# ROM16word.net
KiCad netlist of a schematic drawn in EAGLE
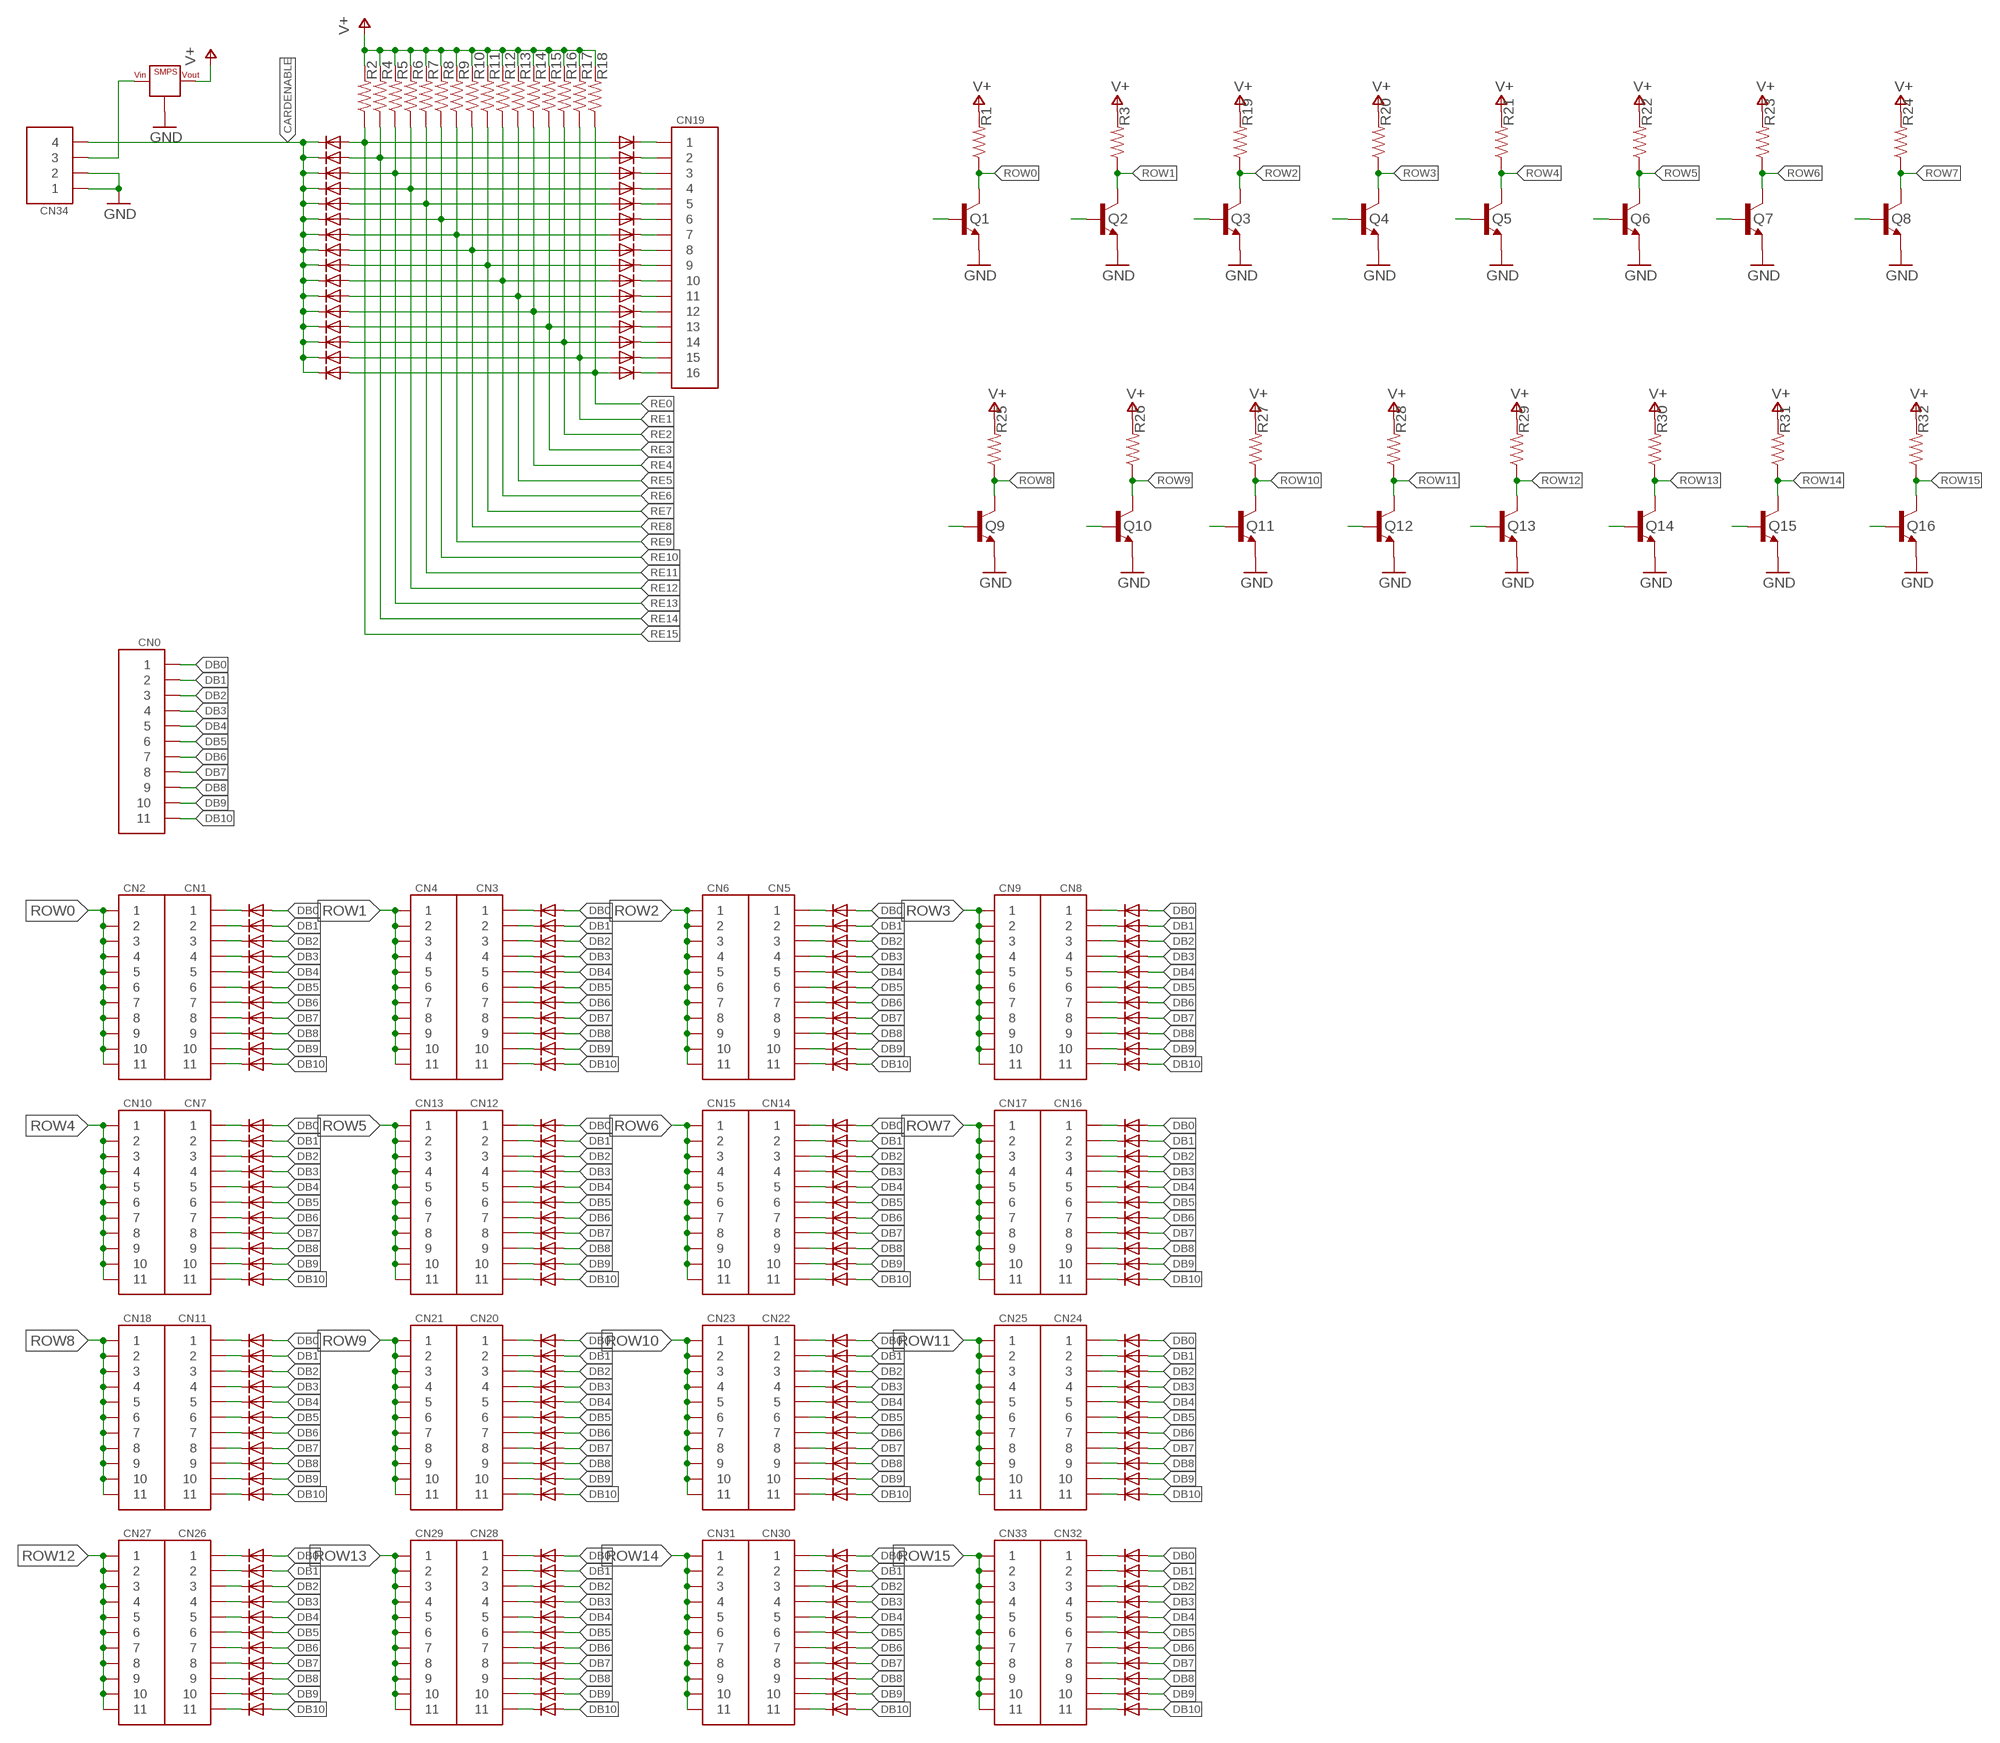
[diagram p0: schematic, sheet 1]

(export (version "E")
  (design (tool "Eeschema 10.0.6"))
  (components
    (comp (ref "CN0")
      (value "HD11")
      (footprint "eagle-import:HD11")
      (libsource (lib "eagle-import") (part "HD11"))
    )
    (comp (ref "CN1")
      (value "HD11")
      (footprint "eagle-import:HD11")
      (libsource (lib "eagle-import") (part "HD11"))
    )
    (comp (ref "CN2")
      (value "HD11")
      (footprint "eagle-import:HD11")
      (libsource (lib "eagle-import") (part "HD11"))
    )
    (comp (ref "CN3")
      (value "HD11")
      (footprint "eagle-import:HD11")
      (libsource (lib "eagle-import") (part "HD11"))
    )
    (comp (ref "CN4")
      (value "HD11")
      (footprint "eagle-import:HD11")
      (libsource (lib "eagle-import") (part "HD11"))
    )
    (comp (ref "CN5")
      (value "HD11")
      (footprint "eagle-import:HD11")
      (libsource (lib "eagle-import") (part "HD11"))
    )
    (comp (ref "CN6")
      (value "HD11")
      (footprint "eagle-import:HD11")
      (libsource (lib "eagle-import") (part "HD11"))
    )
    (comp (ref "CN7")
      (value "HD11")
      (footprint "eagle-import:HD11")
      (libsource (lib "eagle-import") (part "HD11"))
    )
    (comp (ref "CN8")
      (value "HD11")
      (footprint "eagle-import:HD11")
      (libsource (lib "eagle-import") (part "HD11"))
    )
    (comp (ref "CN9")
      (value "HD11")
      (footprint "eagle-import:HD11")
      (libsource (lib "eagle-import") (part "HD11"))
    )
    (comp (ref "CN10")
      (value "HD11")
      (footprint "eagle-import:HD11")
      (libsource (lib "eagle-import") (part "HD11"))
    )
    (comp (ref "CN11")
      (value "HD11")
      (footprint "eagle-import:HD11")
      (libsource (lib "eagle-import") (part "HD11"))
    )
    (comp (ref "CN12")
      (value "HD11")
      (footprint "eagle-import:HD11")
      (libsource (lib "eagle-import") (part "HD11"))
    )
    (comp (ref "CN13")
      (value "HD11")
      (footprint "eagle-import:HD11")
      (libsource (lib "eagle-import") (part "HD11"))
    )
    (comp (ref "CN14")
      (value "HD11")
      (footprint "eagle-import:HD11")
      (libsource (lib "eagle-import") (part "HD11"))
    )
    (comp (ref "CN15")
      (value "HD11")
      (footprint "eagle-import:HD11")
      (libsource (lib "eagle-import") (part "HD11"))
    )
    (comp (ref "CN16")
      (value "HD11")
      (footprint "eagle-import:HD11")
      (libsource (lib "eagle-import") (part "HD11"))
    )
    (comp (ref "CN17")
      (value "HD11")
      (footprint "eagle-import:HD11")
      (libsource (lib "eagle-import") (part "HD11"))
    )
    (comp (ref "CN18")
      (value "HD11")
      (footprint "eagle-import:HD11")
      (libsource (lib "eagle-import") (part "HD11"))
    )
    (comp (ref "CN19")
      (value "HD16")
      (footprint "eagle-import:HD16")
      (libsource (lib "eagle-import") (part "HD16"))
    )
    (comp (ref "CN20")
      (value "HD11")
      (footprint "eagle-import:HD11")
      (libsource (lib "eagle-import") (part "HD11"))
    )
    (comp (ref "CN21")
      (value "HD11")
      (footprint "eagle-import:HD11")
      (libsource (lib "eagle-import") (part "HD11"))
    )
    (comp (ref "CN22")
      (value "HD11")
      (footprint "eagle-import:HD11")
      (libsource (lib "eagle-import") (part "HD11"))
    )
    (comp (ref "CN23")
      (value "HD11")
      (footprint "eagle-import:HD11")
      (libsource (lib "eagle-import") (part "HD11"))
    )
    (comp (ref "CN24")
      (value "HD11")
      (footprint "eagle-import:HD11")
      (libsource (lib "eagle-import") (part "HD11"))
    )
    (comp (ref "CN25")
      (value "HD11")
      (footprint "eagle-import:HD11")
      (libsource (lib "eagle-import") (part "HD11"))
    )
    (comp (ref "CN26")
      (value "HD11")
      (footprint "eagle-import:HD11")
      (libsource (lib "eagle-import") (part "HD11"))
    )
    (comp (ref "CN27")
      (value "HD11")
      (footprint "eagle-import:HD11")
      (libsource (lib "eagle-import") (part "HD11"))
    )
    (comp (ref "CN28")
      (value "HD11")
      (footprint "eagle-import:HD11")
      (libsource (lib "eagle-import") (part "HD11"))
    )
    (comp (ref "CN29")
      (value "HD11")
      (footprint "eagle-import:HD11")
      (libsource (lib "eagle-import") (part "HD11"))
    )
    (comp (ref "CN30")
      (value "HD11")
      (footprint "eagle-import:HD11")
      (libsource (lib "eagle-import") (part "HD11"))
    )
    (comp (ref "CN31")
      (value "HD11")
      (footprint "eagle-import:HD11")
      (libsource (lib "eagle-import") (part "HD11"))
    )
    (comp (ref "CN32")
      (value "HD11")
      (footprint "eagle-import:HD11")
      (libsource (lib "eagle-import") (part "HD11"))
    )
    (comp (ref "CN33")
      (value "HD11")
      (footprint "eagle-import:HD11")
      (libsource (lib "eagle-import") (part "HD11"))
    )
    (comp (ref "CN34")
      (value "HD4")
      (footprint "eagle-import:HD4")
      (libsource (lib "eagle-import") (part "HD4"))
    )
    (comp (ref "D1")
      (value "DIODE-6.3")
      (footprint "eagle-import:DO35-6.3")
      (libsource (lib "eagle-import") (part "DIODE-6.3"))
    )
    (comp (ref "D2")
      (value "DIODE-6.3")
      (footprint "eagle-import:DO35-6.3")
      (libsource (lib "eagle-import") (part "DIODE-6.3"))
    )
    (comp (ref "D3")
      (value "DIODE-6.3")
      (footprint "eagle-import:DO35-6.3")
      (libsource (lib "eagle-import") (part "DIODE-6.3"))
    )
    (comp (ref "D4")
      (value "DIODE-6.3")
      (footprint "eagle-import:DO35-6.3")
      (libsource (lib "eagle-import") (part "DIODE-6.3"))
    )
    (comp (ref "D5")
      (value "DIODE-6.3")
      (footprint "eagle-import:DO35-6.3")
      (libsource (lib "eagle-import") (part "DIODE-6.3"))
    )
    (comp (ref "D6")
      (value "DIODE-6.3")
      (footprint "eagle-import:DO35-6.3")
      (libsource (lib "eagle-import") (part "DIODE-6.3"))
    )
    (comp (ref "D7")
      (value "DIODE-6.3")
      (footprint "eagle-import:DO35-6.3")
      (libsource (lib "eagle-import") (part "DIODE-6.3"))
    )
    (comp (ref "D8")
      (value "DIODE-6.3")
      (footprint "eagle-import:DO35-6.3")
      (libsource (lib "eagle-import") (part "DIODE-6.3"))
    )
    (comp (ref "D9")
      (value "DIODE-6.3")
      (footprint "eagle-import:DO35-6.3")
      (libsource (lib "eagle-import") (part "DIODE-6.3"))
    )
    (comp (ref "D10")
      (value "DIODE-6.3")
      (footprint "eagle-import:DO35-6.3")
      (libsource (lib "eagle-import") (part "DIODE-6.3"))
    )
    (comp (ref "D11")
      (value "DIODE-6.3")
      (footprint "eagle-import:DO35-6.3")
      (libsource (lib "eagle-import") (part "DIODE-6.3"))
    )
    (comp (ref "D12")
      (value "DIODE-6.3")
      (footprint "eagle-import:DO35-6.3")
      (libsource (lib "eagle-import") (part "DIODE-6.3"))
    )
    (comp (ref "D13")
      (value "DIODE-6.3")
      (footprint "eagle-import:DO35-6.3")
      (libsource (lib "eagle-import") (part "DIODE-6.3"))
    )
    (comp (ref "D14")
      (value "DIODE-6.3")
      (footprint "eagle-import:DO35-6.3")
      (libsource (lib "eagle-import") (part "DIODE-6.3"))
    )
    (comp (ref "D15")
      (value "DIODE-6.3")
      (footprint "eagle-import:DO35-6.3")
      (libsource (lib "eagle-import") (part "DIODE-6.3"))
    )
    (comp (ref "D16")
      (value "DIODE-6.3")
      (footprint "eagle-import:DO35-6.3")
      (libsource (lib "eagle-import") (part "DIODE-6.3"))
    )
    (comp (ref "D17")
      (value "DIODE-6.3")
      (footprint "eagle-import:DO35-6.3")
      (libsource (lib "eagle-import") (part "DIODE-6.3"))
    )
    (comp (ref "D18")
      (value "DIODE-6.3")
      (footprint "eagle-import:DO35-6.3")
      (libsource (lib "eagle-import") (part "DIODE-6.3"))
    )
    (comp (ref "D19")
      (value "DIODE-6.3")
      (footprint "eagle-import:DO35-6.3")
      (libsource (lib "eagle-import") (part "DIODE-6.3"))
    )
    (comp (ref "D20")
      (value "DIODE-6.3")
      (footprint "eagle-import:DO35-6.3")
      (libsource (lib "eagle-import") (part "DIODE-6.3"))
    )
    (comp (ref "D21")
      (value "DIODE-6.3")
      (footprint "eagle-import:DO35-6.3")
      (libsource (lib "eagle-import") (part "DIODE-6.3"))
    )
    (comp (ref "D22")
      (value "DIODE-6.3")
      (footprint "eagle-import:DO35-6.3")
      (libsource (lib "eagle-import") (part "DIODE-6.3"))
    )
    (comp (ref "D23")
      (value "DIODE-6.3")
      (footprint "eagle-import:DO35-6.3")
      (libsource (lib "eagle-import") (part "DIODE-6.3"))
    )
    (comp (ref "D24")
      (value "DIODE-6.3")
      (footprint "eagle-import:DO35-6.3")
      (libsource (lib "eagle-import") (part "DIODE-6.3"))
    )
    (comp (ref "D25")
      (value "DIODE-6.3")
      (footprint "eagle-import:DO35-6.3")
      (libsource (lib "eagle-import") (part "DIODE-6.3"))
    )
    (comp (ref "D26")
      (value "DIODE-6.3")
      (footprint "eagle-import:DO35-6.3")
      (libsource (lib "eagle-import") (part "DIODE-6.3"))
    )
    (comp (ref "D27")
      (value "DIODE-6.3")
      (footprint "eagle-import:DO35-6.3")
      (libsource (lib "eagle-import") (part "DIODE-6.3"))
    )
    (comp (ref "D28")
      (value "DIODE-6.3")
      (footprint "eagle-import:DO35-6.3")
      (libsource (lib "eagle-import") (part "DIODE-6.3"))
    )
    (comp (ref "D29")
      (value "DIODE-6.3")
      (footprint "eagle-import:DO35-6.3")
      (libsource (lib "eagle-import") (part "DIODE-6.3"))
    )
    (comp (ref "D30")
      (value "DIODE-6.3")
      (footprint "eagle-import:DO35-6.3")
      (libsource (lib "eagle-import") (part "DIODE-6.3"))
    )
    (comp (ref "D31")
      (value "DIODE-6.3")
      (footprint "eagle-import:DO35-6.3")
      (libsource (lib "eagle-import") (part "DIODE-6.3"))
    )
    (comp (ref "D32")
      (value "DIODE-6.3")
      (footprint "eagle-import:DO35-6.3")
      (libsource (lib "eagle-import") (part "DIODE-6.3"))
    )
    (comp (ref "D33")
      (value "DIODE-6.3")
      (footprint "eagle-import:DO35-6.3")
      (libsource (lib "eagle-import") (part "DIODE-6.3"))
    )
    (comp (ref "D34")
      (value "DIODE-6.3")
      (footprint "eagle-import:DO35-6.3")
      (libsource (lib "eagle-import") (part "DIODE-6.3"))
    )
    (comp (ref "D35")
      (value "DIODE-6.3")
      (footprint "eagle-import:DO35-6.3")
      (libsource (lib "eagle-import") (part "DIODE-6.3"))
    )
    (comp (ref "D36")
      (value "DIODE-6.3")
      (footprint "eagle-import:DO35-6.3")
      (libsource (lib "eagle-import") (part "DIODE-6.3"))
    )
    (comp (ref "D37")
      (value "DIODE-6.3")
      (footprint "eagle-import:DO35-6.3")
      (libsource (lib "eagle-import") (part "DIODE-6.3"))
    )
    (comp (ref "D38")
      (value "DIODE-6.3")
      (footprint "eagle-import:DO35-6.3")
      (libsource (lib "eagle-import") (part "DIODE-6.3"))
    )
    (comp (ref "D39")
      (value "DIODE-6.3")
      (footprint "eagle-import:DO35-6.3")
      (libsource (lib "eagle-import") (part "DIODE-6.3"))
    )
    (comp (ref "D40")
      (value "DIODE-6.3")
      (footprint "eagle-import:DO35-6.3")
      (libsource (lib "eagle-import") (part "DIODE-6.3"))
    )
    (comp (ref "D41")
      (value "DIODE-6.3")
      (footprint "eagle-import:DO35-6.3")
      (libsource (lib "eagle-import") (part "DIODE-6.3"))
    )
    (comp (ref "D42")
      (value "DIODE-6.3")
      (footprint "eagle-import:DO35-6.3")
      (libsource (lib "eagle-import") (part "DIODE-6.3"))
    )
    (comp (ref "D43")
      (value "DIODE-6.3")
      (footprint "eagle-import:DO35-6.3")
      (libsource (lib "eagle-import") (part "DIODE-6.3"))
    )
    (comp (ref "D44")
      (value "DIODE-6.3")
      (footprint "eagle-import:DO35-6.3")
      (libsource (lib "eagle-import") (part "DIODE-6.3"))
    )
    (comp (ref "D45")
      (value "DIODE-6.3")
      (footprint "eagle-import:DO35-6.3")
      (libsource (lib "eagle-import") (part "DIODE-6.3"))
    )
    (comp (ref "D46")
      (value "DIODE-6.3")
      (footprint "eagle-import:DO35-6.3")
      (libsource (lib "eagle-import") (part "DIODE-6.3"))
    )
    (comp (ref "D47")
      (value "DIODE-6.3")
      (footprint "eagle-import:DO35-6.3")
      (libsource (lib "eagle-import") (part "DIODE-6.3"))
    )
    (comp (ref "D48")
      (value "DIODE-6.3")
      (footprint "eagle-import:DO35-6.3")
      (libsource (lib "eagle-import") (part "DIODE-6.3"))
    )
    (comp (ref "D49")
      (value "DIODE-6.3")
      (footprint "eagle-import:DO35-6.3")
      (libsource (lib "eagle-import") (part "DIODE-6.3"))
    )
    (comp (ref "D50")
      (value "DIODE-6.3")
      (footprint "eagle-import:DO35-6.3")
      (libsource (lib "eagle-import") (part "DIODE-6.3"))
    )
    (comp (ref "D51")
      (value "DIODE-6.3")
      (footprint "eagle-import:DO35-6.3")
      (libsource (lib "eagle-import") (part "DIODE-6.3"))
    )
    (comp (ref "D52")
      (value "DIODE-6.3")
      (footprint "eagle-import:DO35-6.3")
      (libsource (lib "eagle-import") (part "DIODE-6.3"))
    )
    (comp (ref "D53")
      (value "DIODE-6.3")
      (footprint "eagle-import:DO35-6.3")
      (libsource (lib "eagle-import") (part "DIODE-6.3"))
    )
    (comp (ref "D54")
      (value "DIODE-6.3")
      (footprint "eagle-import:DO35-6.3")
      (libsource (lib "eagle-import") (part "DIODE-6.3"))
    )
    (comp (ref "D55")
      (value "DIODE-6.3")
      (footprint "eagle-import:DO35-6.3")
      (libsource (lib "eagle-import") (part "DIODE-6.3"))
    )
    (comp (ref "D56")
      (value "DIODE-6.3")
      (footprint "eagle-import:DO35-6.3")
      (libsource (lib "eagle-import") (part "DIODE-6.3"))
    )
    (comp (ref "D57")
      (value "DIODE-6.3")
      (footprint "eagle-import:DO35-6.3")
      (libsource (lib "eagle-import") (part "DIODE-6.3"))
    )
    (comp (ref "D58")
      (value "DIODE-6.3")
      (footprint "eagle-import:DO35-6.3")
      (libsource (lib "eagle-import") (part "DIODE-6.3"))
    )
    (comp (ref "D59")
      (value "DIODE-6.3")
      (footprint "eagle-import:DO35-6.3")
      (libsource (lib "eagle-import") (part "DIODE-6.3"))
    )
    (comp (ref "D60")
      (value "DIODE-6.3")
      (footprint "eagle-import:DO35-6.3")
      (libsource (lib "eagle-import") (part "DIODE-6.3"))
    )
    (comp (ref "D61")
      (value "DIODE-6.3")
      (footprint "eagle-import:DO35-6.3")
      (libsource (lib "eagle-import") (part "DIODE-6.3"))
    )
    (comp (ref "D62")
      (value "DIODE-6.3")
      (footprint "eagle-import:DO35-6.3")
      (libsource (lib "eagle-import") (part "DIODE-6.3"))
    )
    (comp (ref "D63")
      (value "DIODE-6.3")
      (footprint "eagle-import:DO35-6.3")
      (libsource (lib "eagle-import") (part "DIODE-6.3"))
    )
    (comp (ref "D64")
      (value "DIODE-6.3")
      (footprint "eagle-import:DO35-6.3")
      (libsource (lib "eagle-import") (part "DIODE-6.3"))
    )
    (comp (ref "D65")
      (value "DIODE-6.3")
      (footprint "eagle-import:DO35-6.3")
      (libsource (lib "eagle-import") (part "DIODE-6.3"))
    )
    (comp (ref "D66")
      (value "DIODE-6.3")
      (footprint "eagle-import:DO35-6.3")
      (libsource (lib "eagle-import") (part "DIODE-6.3"))
    )
    (comp (ref "D67")
      (value "DIODE-6.3")
      (footprint "eagle-import:DO35-6.3")
      (libsource (lib "eagle-import") (part "DIODE-6.3"))
    )
    (comp (ref "D68")
      (value "DIODE-6.3")
      (footprint "eagle-import:DO35-6.3")
      (libsource (lib "eagle-import") (part "DIODE-6.3"))
    )
    (comp (ref "D69")
      (value "DIODE-6.3")
      (footprint "eagle-import:DO35-6.3")
      (libsource (lib "eagle-import") (part "DIODE-6.3"))
    )
    (comp (ref "D70")
      (value "DIODE-6.3")
      (footprint "eagle-import:DO35-6.3")
      (libsource (lib "eagle-import") (part "DIODE-6.3"))
    )
    (comp (ref "D71")
      (value "DIODE-6.3")
      (footprint "eagle-import:DO35-6.3")
      (libsource (lib "eagle-import") (part "DIODE-6.3"))
    )
    (comp (ref "D72")
      (value "DIODE-6.3")
      (footprint "eagle-import:DO35-6.3")
      (libsource (lib "eagle-import") (part "DIODE-6.3"))
    )
    (comp (ref "D73")
      (value "DIODE-6.3")
      (footprint "eagle-import:DO35-6.3")
      (libsource (lib "eagle-import") (part "DIODE-6.3"))
    )
    (comp (ref "D74")
      (value "DIODE-6.3")
      (footprint "eagle-import:DO35-6.3")
      (libsource (lib "eagle-import") (part "DIODE-6.3"))
    )
    (comp (ref "D75")
      (value "DIODE-6.3")
      (footprint "eagle-import:DO35-6.3")
      (libsource (lib "eagle-import") (part "DIODE-6.3"))
    )
    (comp (ref "D76")
      (value "DIODE-6.3")
      (footprint "eagle-import:DO35-6.3")
      (libsource (lib "eagle-import") (part "DIODE-6.3"))
    )
    (comp (ref "D77")
      (value "DIODE-6.3")
      (footprint "eagle-import:DO35-6.3")
      (libsource (lib "eagle-import") (part "DIODE-6.3"))
    )
    (comp (ref "D78")
      (value "DIODE-6.3")
      (footprint "eagle-import:DO35-6.3")
      (libsource (lib "eagle-import") (part "DIODE-6.3"))
    )
    (comp (ref "D79")
      (value "DIODE-6.3")
      (footprint "eagle-import:DO35-6.3")
      (libsource (lib "eagle-import") (part "DIODE-6.3"))
    )
    (comp (ref "D80")
      (value "DIODE-6.3")
      (footprint "eagle-import:DO35-6.3")
      (libsource (lib "eagle-import") (part "DIODE-6.3"))
    )
    (comp (ref "D81")
      (value "DIODE-6.3")
      (footprint "eagle-import:DO35-6.3")
      (libsource (lib "eagle-import") (part "DIODE-6.3"))
    )
    (comp (ref "D82")
      (value "DIODE-6.3")
      (footprint "eagle-import:DO35-6.3")
      (libsource (lib "eagle-import") (part "DIODE-6.3"))
    )
    (comp (ref "D83")
      (value "DIODE-6.3")
      (footprint "eagle-import:DO35-6.3")
      (libsource (lib "eagle-import") (part "DIODE-6.3"))
    )
    (comp (ref "D84")
      (value "DIODE-6.3")
      (footprint "eagle-import:DO35-6.3")
      (libsource (lib "eagle-import") (part "DIODE-6.3"))
    )
    (comp (ref "D85")
      (value "DIODE-6.3")
      (footprint "eagle-import:DO35-6.3")
      (libsource (lib "eagle-import") (part "DIODE-6.3"))
    )
    (comp (ref "D86")
      (value "DIODE-6.3")
      (footprint "eagle-import:DO35-6.3")
      (libsource (lib "eagle-import") (part "DIODE-6.3"))
    )
    (comp (ref "D87")
      (value "DIODE-6.3")
      (footprint "eagle-import:DO35-6.3")
      (libsource (lib "eagle-import") (part "DIODE-6.3"))
    )
    (comp (ref "D88")
      (value "DIODE-6.3")
      (footprint "eagle-import:DO35-6.3")
      (libsource (lib "eagle-import") (part "DIODE-6.3"))
    )
    (comp (ref "D89")
      (value "DIODE-6.3")
      (footprint "eagle-import:DO35-6.3")
      (libsource (lib "eagle-import") (part "DIODE-6.3"))
    )
    (comp (ref "D90")
      (value "DIODE-6.3")
      (footprint "eagle-import:DO35-6.3")
      (libsource (lib "eagle-import") (part "DIODE-6.3"))
    )
    (comp (ref "D91")
      (value "DIODE-6.3")
      (footprint "eagle-import:DO35-6.3")
      (libsource (lib "eagle-import") (part "DIODE-6.3"))
    )
    (comp (ref "D92")
      (value "DIODE-6.3")
      (footprint "eagle-import:DO35-6.3")
      (libsource (lib "eagle-import") (part "DIODE-6.3"))
    )
    (comp (ref "D93")
      (value "DIODE-6.3")
      (footprint "eagle-import:DO35-6.3")
      (libsource (lib "eagle-import") (part "DIODE-6.3"))
    )
    (comp (ref "D94")
      (value "DIODE-6.3")
      (footprint "eagle-import:DO35-6.3")
      (libsource (lib "eagle-import") (part "DIODE-6.3"))
    )
    (comp (ref "D95")
      (value "DIODE-6.3")
      (footprint "eagle-import:DO35-6.3")
      (libsource (lib "eagle-import") (part "DIODE-6.3"))
    )
    (comp (ref "D96")
      (value "DIODE-6.3")
      (footprint "eagle-import:DO35-6.3")
      (libsource (lib "eagle-import") (part "DIODE-6.3"))
    )
    (comp (ref "D97")
      (value "DIODE-6.3")
      (footprint "eagle-import:DO35-6.3")
      (libsource (lib "eagle-import") (part "DIODE-6.3"))
    )
    (comp (ref "D98")
      (value "DIODE-6.3")
      (footprint "eagle-import:DO35-6.3")
      (libsource (lib "eagle-import") (part "DIODE-6.3"))
    )
    (comp (ref "D99")
      (value "DIODE-6.3")
      (footprint "eagle-import:DO35-6.3")
      (libsource (lib "eagle-import") (part "DIODE-6.3"))
    )
    (comp (ref "D100")
      (value "DIODE-6.3")
      (footprint "eagle-import:DO35-6.3")
      (libsource (lib "eagle-import") (part "DIODE-6.3"))
    )
    (comp (ref "D101")
      (value "DIODE-6.3")
      (footprint "eagle-import:DO35-6.3")
      (libsource (lib "eagle-import") (part "DIODE-6.3"))
    )
    (comp (ref "D102")
      (value "DIODE-6.3")
      (footprint "eagle-import:DO35-6.3")
      (libsource (lib "eagle-import") (part "DIODE-6.3"))
    )
    (comp (ref "D103")
      (value "DIODE-6.3")
      (footprint "eagle-import:DO35-6.3")
      (libsource (lib "eagle-import") (part "DIODE-6.3"))
    )
    (comp (ref "D104")
      (value "DIODE-6.3")
      (footprint "eagle-import:DO35-6.3")
      (libsource (lib "eagle-import") (part "DIODE-6.3"))
    )
    (comp (ref "D105")
      (value "DIODE-6.3")
      (footprint "eagle-import:DO35-6.3")
      (libsource (lib "eagle-import") (part "DIODE-6.3"))
    )
    (comp (ref "D106")
      (value "DIODE-6.3")
      (footprint "eagle-import:DO35-6.3")
      (libsource (lib "eagle-import") (part "DIODE-6.3"))
    )
    (comp (ref "D107")
      (value "DIODE-6.3")
      (footprint "eagle-import:DO35-6.3")
      (libsource (lib "eagle-import") (part "DIODE-6.3"))
    )
    (comp (ref "D108")
      (value "DIODE-6.3")
      (footprint "eagle-import:DO35-6.3")
      (libsource (lib "eagle-import") (part "DIODE-6.3"))
    )
    (comp (ref "D109")
      (value "DIODE-6.3")
      (footprint "eagle-import:DO35-6.3")
      (libsource (lib "eagle-import") (part "DIODE-6.3"))
    )
    (comp (ref "D110")
      (value "DIODE-6.3")
      (footprint "eagle-import:DO35-6.3")
      (libsource (lib "eagle-import") (part "DIODE-6.3"))
    )
    (comp (ref "D111")
      (value "DIODE-6.3")
      (footprint "eagle-import:DO35-6.3")
      (libsource (lib "eagle-import") (part "DIODE-6.3"))
    )
    (comp (ref "D112")
      (value "DIODE-6.3")
      (footprint "eagle-import:DO35-6.3")
      (libsource (lib "eagle-import") (part "DIODE-6.3"))
    )
    (comp (ref "D113")
      (value "DIODE-6.3")
      (footprint "eagle-import:DO35-6.3")
      (libsource (lib "eagle-import") (part "DIODE-6.3"))
    )
    (comp (ref "D114")
      (value "DIODE-6.3")
      (footprint "eagle-import:DO35-6.3")
      (libsource (lib "eagle-import") (part "DIODE-6.3"))
    )
    (comp (ref "D115")
      (value "DIODE-6.3")
      (footprint "eagle-import:DO35-6.3")
      (libsource (lib "eagle-import") (part "DIODE-6.3"))
    )
    (comp (ref "D116")
      (value "DIODE-6.3")
      (footprint "eagle-import:DO35-6.3")
      (libsource (lib "eagle-import") (part "DIODE-6.3"))
    )
    (comp (ref "D117")
      (value "DIODE-6.3")
      (footprint "eagle-import:DO35-6.3")
      (libsource (lib "eagle-import") (part "DIODE-6.3"))
    )
    (comp (ref "D118")
      (value "DIODE-6.3")
      (footprint "eagle-import:DO35-6.3")
      (libsource (lib "eagle-import") (part "DIODE-6.3"))
    )
    (comp (ref "D119")
      (value "DIODE-6.3")
      (footprint "eagle-import:DO35-6.3")
      (libsource (lib "eagle-import") (part "DIODE-6.3"))
    )
    (comp (ref "D120")
      (value "DIODE-6.3")
      (footprint "eagle-import:DO35-6.3")
      (libsource (lib "eagle-import") (part "DIODE-6.3"))
    )
    (comp (ref "D121")
      (value "DIODE-6.3")
      (footprint "eagle-import:DO35-6.3")
      (libsource (lib "eagle-import") (part "DIODE-6.3"))
    )
    (comp (ref "D122")
      (value "DIODE-6.3")
      (footprint "eagle-import:DO35-6.3")
      (libsource (lib "eagle-import") (part "DIODE-6.3"))
    )
    (comp (ref "D123")
      (value "DIODE-6.3")
      (footprint "eagle-import:DO35-6.3")
      (libsource (lib "eagle-import") (part "DIODE-6.3"))
    )
    (comp (ref "D124")
      (value "DIODE-6.3")
      (footprint "eagle-import:DO35-6.3")
      (libsource (lib "eagle-import") (part "DIODE-6.3"))
    )
    (comp (ref "D125")
      (value "DIODE-6.3")
      (footprint "eagle-import:DO35-6.3")
      (libsource (lib "eagle-import") (part "DIODE-6.3"))
    )
    (comp (ref "D126")
      (value "DIODE-6.3")
      (footprint "eagle-import:DO35-6.3")
      (libsource (lib "eagle-import") (part "DIODE-6.3"))
    )
    (comp (ref "D127")
      (value "DIODE-6.3")
      (footprint "eagle-import:DO35-6.3")
      (libsource (lib "eagle-import") (part "DIODE-6.3"))
    )
    (comp (ref "D128")
      (value "DIODE-6.3")
      (footprint "eagle-import:DO35-6.3")
      (libsource (lib "eagle-import") (part "DIODE-6.3"))
    )
    (comp (ref "D129")
      (value "DIODE-6.3")
      (footprint "eagle-import:DO35-6.3")
      (libsource (lib "eagle-import") (part "DIODE-6.3"))
    )
    (comp (ref "D130")
      (value "DIODE-6.3")
      (footprint "eagle-import:DO35-6.3")
      (libsource (lib "eagle-import") (part "DIODE-6.3"))
    )
    (comp (ref "D131")
      (value "DIODE-6.3")
      (footprint "eagle-import:DO35-6.3")
      (libsource (lib "eagle-import") (part "DIODE-6.3"))
    )
    (comp (ref "D132")
      (value "DIODE-6.3")
      (footprint "eagle-import:DO35-6.3")
      (libsource (lib "eagle-import") (part "DIODE-6.3"))
    )
    (comp (ref "D133")
      (value "DIODE-6.3")
      (footprint "eagle-import:DO35-6.3")
      (libsource (lib "eagle-import") (part "DIODE-6.3"))
    )
    (comp (ref "D134")
      (value "DIODE-6.3")
      (footprint "eagle-import:DO35-6.3")
      (libsource (lib "eagle-import") (part "DIODE-6.3"))
    )
    (comp (ref "D135")
      (value "DIODE-6.3")
      (footprint "eagle-import:DO35-6.3")
      (libsource (lib "eagle-import") (part "DIODE-6.3"))
    )
    (comp (ref "D136")
      (value "DIODE-6.3")
      (footprint "eagle-import:DO35-6.3")
      (libsource (lib "eagle-import") (part "DIODE-6.3"))
    )
    (comp (ref "D137")
      (value "DIODE-6.3")
      (footprint "eagle-import:DO35-6.3")
      (libsource (lib "eagle-import") (part "DIODE-6.3"))
    )
    (comp (ref "D138")
      (value "DIODE-6.3")
      (footprint "eagle-import:DO35-6.3")
      (libsource (lib "eagle-import") (part "DIODE-6.3"))
    )
    (comp (ref "D139")
      (value "DIODE-6.3")
      (footprint "eagle-import:DO35-6.3")
      (libsource (lib "eagle-import") (part "DIODE-6.3"))
    )
    (comp (ref "D140")
      (value "DIODE-6.3")
      (footprint "eagle-import:DO35-6.3")
      (libsource (lib "eagle-import") (part "DIODE-6.3"))
    )
    (comp (ref "D141")
      (value "DIODE-6.3")
      (footprint "eagle-import:DO35-6.3")
      (libsource (lib "eagle-import") (part "DIODE-6.3"))
    )
    (comp (ref "D142")
      (value "DIODE-6.3")
      (footprint "eagle-import:DO35-6.3")
      (libsource (lib "eagle-import") (part "DIODE-6.3"))
    )
    (comp (ref "D143")
      (value "DIODE-6.3")
      (footprint "eagle-import:DO35-6.3")
      (libsource (lib "eagle-import") (part "DIODE-6.3"))
    )
    (comp (ref "D144")
      (value "DIODE-6.3")
      (footprint "eagle-import:DO35-6.3")
      (libsource (lib "eagle-import") (part "DIODE-6.3"))
    )
    (comp (ref "D145")
      (value "DIODE-6.3")
      (footprint "eagle-import:DO35-6.3")
      (libsource (lib "eagle-import") (part "DIODE-6.3"))
    )
    (comp (ref "D146")
      (value "DIODE-6.3")
      (footprint "eagle-import:DO35-6.3")
      (libsource (lib "eagle-import") (part "DIODE-6.3"))
    )
    (comp (ref "D147")
      (value "DIODE-6.3")
      (footprint "eagle-import:DO35-6.3")
      (libsource (lib "eagle-import") (part "DIODE-6.3"))
    )
    (comp (ref "D148")
      (value "DIODE-6.3")
      (footprint "eagle-import:DO35-6.3")
      (libsource (lib "eagle-import") (part "DIODE-6.3"))
    )
    (comp (ref "D149")
      (value "DIODE-6.3")
      (footprint "eagle-import:DO35-6.3")
      (libsource (lib "eagle-import") (part "DIODE-6.3"))
    )
    (comp (ref "D150")
      (value "DIODE-6.3")
      (footprint "eagle-import:DO35-6.3")
      (libsource (lib "eagle-import") (part "DIODE-6.3"))
    )
    (comp (ref "D151")
      (value "DIODE-6.3")
      (footprint "eagle-import:DO35-6.3")
      (libsource (lib "eagle-import") (part "DIODE-6.3"))
    )
    (comp (ref "D152")
      (value "DIODE-6.3")
      (footprint "eagle-import:DO35-6.3")
      (libsource (lib "eagle-import") (part "DIODE-6.3"))
    )
    (comp (ref "D153")
      (value "DIODE-6.3")
      (footprint "eagle-import:DO35-6.3")
      (libsource (lib "eagle-import") (part "DIODE-6.3"))
    )
    (comp (ref "D154")
      (value "DIODE-6.3")
      (footprint "eagle-import:DO35-6.3")
      (libsource (lib "eagle-import") (part "DIODE-6.3"))
    )
    (comp (ref "D155")
      (value "DIODE-6.3")
      (footprint "eagle-import:DO35-6.3")
      (libsource (lib "eagle-import") (part "DIODE-6.3"))
    )
    (comp (ref "D156")
      (value "DIODE-6.3")
      (footprint "eagle-import:DO35-6.3")
      (libsource (lib "eagle-import") (part "DIODE-6.3"))
    )
    (comp (ref "D157")
      (value "DIODE-6.3")
      (footprint "eagle-import:DO35-6.3")
      (libsource (lib "eagle-import") (part "DIODE-6.3"))
    )
    (comp (ref "D158")
      (value "DIODE-6.3")
      (footprint "eagle-import:DO35-6.3")
      (libsource (lib "eagle-import") (part "DIODE-6.3"))
    )
    (comp (ref "D159")
      (value "DIODE-6.3")
      (footprint "eagle-import:DO35-6.3")
      (libsource (lib "eagle-import") (part "DIODE-6.3"))
    )
    (comp (ref "D160")
      (value "DIODE-6.3")
      (footprint "eagle-import:DO35-6.3")
      (libsource (lib "eagle-import") (part "DIODE-6.3"))
    )
    (comp (ref "D161")
      (value "DIODE-6.3")
      (footprint "eagle-import:DO35-6.3")
      (libsource (lib "eagle-import") (part "DIODE-6.3"))
    )
    (comp (ref "D162")
      (value "DIODE-6.3")
      (footprint "eagle-import:DO35-6.3")
      (libsource (lib "eagle-import") (part "DIODE-6.3"))
    )
    (comp (ref "D163")
      (value "DIODE-6.3")
      (footprint "eagle-import:DO35-6.3")
      (libsource (lib "eagle-import") (part "DIODE-6.3"))
    )
    (comp (ref "D164")
      (value "DIODE-6.3")
      (footprint "eagle-import:DO35-6.3")
      (libsource (lib "eagle-import") (part "DIODE-6.3"))
    )
    (comp (ref "D165")
      (value "DIODE-6.3")
      (footprint "eagle-import:DO35-6.3")
      (libsource (lib "eagle-import") (part "DIODE-6.3"))
    )
    (comp (ref "D166")
      (value "DIODE-6.3")
      (footprint "eagle-import:DO35-6.3")
      (libsource (lib "eagle-import") (part "DIODE-6.3"))
    )
    (comp (ref "D167")
      (value "DIODE-6.3")
      (footprint "eagle-import:DO35-6.3")
      (libsource (lib "eagle-import") (part "DIODE-6.3"))
    )
    (comp (ref "D168")
      (value "DIODE-6.3")
      (footprint "eagle-import:DO35-6.3")
      (libsource (lib "eagle-import") (part "DIODE-6.3"))
    )
    (comp (ref "D169")
      (value "DIODE-6.3")
      (footprint "eagle-import:DO35-6.3")
      (libsource (lib "eagle-import") (part "DIODE-6.3"))
    )
    (comp (ref "D170")
      (value "DIODE-6.3")
      (footprint "eagle-import:DO35-6.3")
      (libsource (lib "eagle-import") (part "DIODE-6.3"))
    )
    (comp (ref "D171")
      (value "DIODE-6.3")
      (footprint "eagle-import:DO35-6.3")
      (libsource (lib "eagle-import") (part "DIODE-6.3"))
    )
    (comp (ref "D172")
      (value "DIODE-6.3")
      (footprint "eagle-import:DO35-6.3")
      (libsource (lib "eagle-import") (part "DIODE-6.3"))
    )
    (comp (ref "D173")
      (value "DIODE-6.3")
      (footprint "eagle-import:DO35-6.3")
      (libsource (lib "eagle-import") (part "DIODE-6.3"))
    )
    (comp (ref "D174")
      (value "DIODE-6.3")
      (footprint "eagle-import:DO35-6.3")
      (libsource (lib "eagle-import") (part "DIODE-6.3"))
    )
    (comp (ref "D175")
      (value "DIODE-6.3")
      (footprint "eagle-import:DO35-6.3")
      (libsource (lib "eagle-import") (part "DIODE-6.3"))
    )
    (comp (ref "D176")
      (value "DIODE-6.3")
      (footprint "eagle-import:DO35-6.3")
      (libsource (lib "eagle-import") (part "DIODE-6.3"))
    )
    (comp (ref "D177")
      (value "DIODE-5.08")
      (footprint "eagle-import:DO35-5.08")
      (libsource (lib "eagle-import") (part "DIODE-5.08"))
    )
    (comp (ref "D178")
      (value "DIODE-5.08")
      (footprint "eagle-import:DO35-5.08")
      (libsource (lib "eagle-import") (part "DIODE-5.08"))
    )
    (comp (ref "D179")
      (value "DIODE-5.08")
      (footprint "eagle-import:DO35-5.08")
      (libsource (lib "eagle-import") (part "DIODE-5.08"))
    )
    (comp (ref "D180")
      (value "DIODE-5.08")
      (footprint "eagle-import:DO35-5.08")
      (libsource (lib "eagle-import") (part "DIODE-5.08"))
    )
    (comp (ref "D181")
      (value "DIODE-5.08")
      (footprint "eagle-import:DO35-5.08")
      (libsource (lib "eagle-import") (part "DIODE-5.08"))
    )
    (comp (ref "D182")
      (value "DIODE-5.08")
      (footprint "eagle-import:DO35-5.08")
      (libsource (lib "eagle-import") (part "DIODE-5.08"))
    )
    (comp (ref "D183")
      (value "DIODE-5.08")
      (footprint "eagle-import:DO35-5.08")
      (libsource (lib "eagle-import") (part "DIODE-5.08"))
    )
    (comp (ref "D184")
      (value "DIODE-5.08")
      (footprint "eagle-import:DO35-5.08")
      (libsource (lib "eagle-import") (part "DIODE-5.08"))
    )
    (comp (ref "D185")
      (value "DIODE-5.08")
      (footprint "eagle-import:DO35-5.08")
      (libsource (lib "eagle-import") (part "DIODE-5.08"))
    )
    (comp (ref "D186")
      (value "DIODE-5.08")
      (footprint "eagle-import:DO35-5.08")
      (libsource (lib "eagle-import") (part "DIODE-5.08"))
    )
    (comp (ref "D187")
      (value "DIODE-5.08")
      (footprint "eagle-import:DO35-5.08")
      (libsource (lib "eagle-import") (part "DIODE-5.08"))
    )
    (comp (ref "D188")
      (value "DIODE-5.08")
      (footprint "eagle-import:DO35-5.08")
      (libsource (lib "eagle-import") (part "DIODE-5.08"))
    )
    (comp (ref "D189")
      (value "DIODE-5.08")
      (footprint "eagle-import:DO35-5.08")
      (libsource (lib "eagle-import") (part "DIODE-5.08"))
    )
    (comp (ref "D190")
      (value "DIODE-5.08")
      (footprint "eagle-import:DO35-5.08")
      (libsource (lib "eagle-import") (part "DIODE-5.08"))
    )
    (comp (ref "D191")
      (value "DIODE-5.08")
      (footprint "eagle-import:DO35-5.08")
      (libsource (lib "eagle-import") (part "DIODE-5.08"))
    )
    (comp (ref "D192")
      (value "DIODE-5.08")
      (footprint "eagle-import:DO35-5.08")
      (libsource (lib "eagle-import") (part "DIODE-5.08"))
    )
    (comp (ref "D193")
      (value "DIODE-5.08")
      (footprint "eagle-import:DO35-5.08")
      (libsource (lib "eagle-import") (part "DIODE-5.08"))
    )
    (comp (ref "D194")
      (value "DIODE-5.08")
      (footprint "eagle-import:DO35-5.08")
      (libsource (lib "eagle-import") (part "DIODE-5.08"))
    )
    (comp (ref "D195")
      (value "DIODE-5.08")
      (footprint "eagle-import:DO35-5.08")
      (libsource (lib "eagle-import") (part "DIODE-5.08"))
    )
    (comp (ref "D196")
      (value "DIODE-5.08")
      (footprint "eagle-import:DO35-5.08")
      (libsource (lib "eagle-import") (part "DIODE-5.08"))
    )
    (comp (ref "D197")
      (value "DIODE-5.08")
      (footprint "eagle-import:DO35-5.08")
      (libsource (lib "eagle-import") (part "DIODE-5.08"))
    )
    (comp (ref "D198")
      (value "DIODE-5.08")
      (footprint "eagle-import:DO35-5.08")
      (libsource (lib "eagle-import") (part "DIODE-5.08"))
    )
    (comp (ref "D199")
      (value "DIODE-5.08")
      (footprint "eagle-import:DO35-5.08")
      (libsource (lib "eagle-import") (part "DIODE-5.08"))
    )
    (comp (ref "D200")
      (value "DIODE-5.08")
      (footprint "eagle-import:DO35-5.08")
      (libsource (lib "eagle-import") (part "DIODE-5.08"))
    )
    (comp (ref "D201")
      (value "DIODE-5.08")
      (footprint "eagle-import:DO35-5.08")
      (libsource (lib "eagle-import") (part "DIODE-5.08"))
    )
    (comp (ref "D202")
      (value "DIODE-5.08")
      (footprint "eagle-import:DO35-5.08")
      (libsource (lib "eagle-import") (part "DIODE-5.08"))
    )
    (comp (ref "D203")
      (value "DIODE-5.08")
      (footprint "eagle-import:DO35-5.08")
      (libsource (lib "eagle-import") (part "DIODE-5.08"))
    )
    (comp (ref "D204")
      (value "DIODE-5.08")
      (footprint "eagle-import:DO35-5.08")
      (libsource (lib "eagle-import") (part "DIODE-5.08"))
    )
    (comp (ref "D205")
      (value "DIODE-5.08")
      (footprint "eagle-import:DO35-5.08")
      (libsource (lib "eagle-import") (part "DIODE-5.08"))
    )
    (comp (ref "D206")
      (value "DIODE-5.08")
      (footprint "eagle-import:DO35-5.08")
      (libsource (lib "eagle-import") (part "DIODE-5.08"))
    )
    (comp (ref "D207")
      (value "DIODE-5.08")
      (footprint "eagle-import:DO35-5.08")
      (libsource (lib "eagle-import") (part "DIODE-5.08"))
    )
    (comp (ref "D208")
      (value "DIODE-5.08")
      (footprint "eagle-import:DO35-5.08")
      (libsource (lib "eagle-import") (part "DIODE-5.08"))
    )
    (comp (ref "Q1")
      (value "BC547-STRAIGHT")
      (footprint "eagle-import:TO92-S-CBE")
      (libsource (lib "eagle-import") (part "BC547-STRAIGHT"))
    )
    (comp (ref "Q2")
      (value "BC547-STRAIGHT")
      (footprint "eagle-import:TO92-S-CBE")
      (libsource (lib "eagle-import") (part "BC547-STRAIGHT"))
    )
    (comp (ref "Q3")
      (value "BC547-STRAIGHT")
      (footprint "eagle-import:TO92-S-CBE")
      (libsource (lib "eagle-import") (part "BC547-STRAIGHT"))
    )
    (comp (ref "Q4")
      (value "BC547-STRAIGHT")
      (footprint "eagle-import:TO92-S-CBE")
      (libsource (lib "eagle-import") (part "BC547-STRAIGHT"))
    )
    (comp (ref "Q5")
      (value "BC547-STRAIGHT")
      (footprint "eagle-import:TO92-S-CBE")
      (libsource (lib "eagle-import") (part "BC547-STRAIGHT"))
    )
    (comp (ref "Q6")
      (value "BC547-STRAIGHT")
      (footprint "eagle-import:TO92-S-CBE")
      (libsource (lib "eagle-import") (part "BC547-STRAIGHT"))
    )
    (comp (ref "Q7")
      (value "BC547-STRAIGHT")
      (footprint "eagle-import:TO92-S-CBE")
      (libsource (lib "eagle-import") (part "BC547-STRAIGHT"))
    )
    (comp (ref "Q8")
      (value "BC547-STRAIGHT")
      (footprint "eagle-import:TO92-S-CBE")
      (libsource (lib "eagle-import") (part "BC547-STRAIGHT"))
    )
    (comp (ref "Q9")
      (value "BC547-STRAIGHT")
      (footprint "eagle-import:TO92-S-CBE")
      (libsource (lib "eagle-import") (part "BC547-STRAIGHT"))
    )
    (comp (ref "Q10")
      (value "BC547-STRAIGHT")
      (footprint "eagle-import:TO92-S-CBE")
      (libsource (lib "eagle-import") (part "BC547-STRAIGHT"))
    )
    (comp (ref "Q11")
      (value "BC547-STRAIGHT")
      (footprint "eagle-import:TO92-S-CBE")
      (libsource (lib "eagle-import") (part "BC547-STRAIGHT"))
    )
    (comp (ref "Q12")
      (value "BC547-STRAIGHT")
      (footprint "eagle-import:TO92-S-CBE")
      (libsource (lib "eagle-import") (part "BC547-STRAIGHT"))
    )
    (comp (ref "Q13")
      (value "BC547-STRAIGHT")
      (footprint "eagle-import:TO92-S-CBE")
      (libsource (lib "eagle-import") (part "BC547-STRAIGHT"))
    )
    (comp (ref "Q14")
      (value "BC547-STRAIGHT")
      (footprint "eagle-import:TO92-S-CBE")
      (libsource (lib "eagle-import") (part "BC547-STRAIGHT"))
    )
    (comp (ref "Q15")
      (value "BC547-STRAIGHT")
      (footprint "eagle-import:TO92-S-CBE")
      (libsource (lib "eagle-import") (part "BC547-STRAIGHT"))
    )
    (comp (ref "Q16")
      (value "BC547-STRAIGHT")
      (footprint "eagle-import:TO92-S-CBE")
      (libsource (lib "eagle-import") (part "BC547-STRAIGHT"))
    )
    (comp (ref "R1")
      (value "R1/8-6MM")
      (footprint "eagle-import:R0125-6.3")
      (libsource (lib "eagle-import") (part "R1/8-6MM"))
    )
    (comp (ref "R2")
      (value "R1/8-6MM")
      (footprint "eagle-import:R0125-6.3")
      (libsource (lib "eagle-import") (part "R1/8-6MM"))
    )
    (comp (ref "R3")
      (value "R1/8-6MM")
      (footprint "eagle-import:R0125-6.3")
      (libsource (lib "eagle-import") (part "R1/8-6MM"))
    )
    (comp (ref "R4")
      (value "R1/8-6MM")
      (footprint "eagle-import:R0125-6.3")
      (libsource (lib "eagle-import") (part "R1/8-6MM"))
    )
    (comp (ref "R5")
      (value "R1/8-6MM")
      (footprint "eagle-import:R0125-6.3")
      (libsource (lib "eagle-import") (part "R1/8-6MM"))
    )
    (comp (ref "R6")
      (value "R1/8-6MM")
      (footprint "eagle-import:R0125-6.3")
      (libsource (lib "eagle-import") (part "R1/8-6MM"))
    )
    (comp (ref "R7")
      (value "R1/8-6MM")
      (footprint "eagle-import:R0125-6.3")
      (libsource (lib "eagle-import") (part "R1/8-6MM"))
    )
    (comp (ref "R8")
      (value "R1/8-6MM")
      (footprint "eagle-import:R0125-6.3")
      (libsource (lib "eagle-import") (part "R1/8-6MM"))
    )
    (comp (ref "R9")
      (value "R1/8-6MM")
      (footprint "eagle-import:R0125-6.3")
      (libsource (lib "eagle-import") (part "R1/8-6MM"))
    )
    (comp (ref "R10")
      (value "R1/8-6MM")
      (footprint "eagle-import:R0125-6.3")
      (libsource (lib "eagle-import") (part "R1/8-6MM"))
    )
    (comp (ref "R11")
      (value "R1/8-6MM")
      (footprint "eagle-import:R0125-6.3")
      (libsource (lib "eagle-import") (part "R1/8-6MM"))
    )
    (comp (ref "R12")
      (value "R1/8-6MM")
      (footprint "eagle-import:R0125-6.3")
      (libsource (lib "eagle-import") (part "R1/8-6MM"))
    )
    (comp (ref "R13")
      (value "R1/8-6MM")
      (footprint "eagle-import:R0125-6.3")
      (libsource (lib "eagle-import") (part "R1/8-6MM"))
    )
    (comp (ref "R14")
      (value "R1/8-6MM")
      (footprint "eagle-import:R0125-6.3")
      (libsource (lib "eagle-import") (part "R1/8-6MM"))
    )
    (comp (ref "R15")
      (value "R1/8-6MM")
      (footprint "eagle-import:R0125-6.3")
      (libsource (lib "eagle-import") (part "R1/8-6MM"))
    )
    (comp (ref "R16")
      (value "R1/8-6MM")
      (footprint "eagle-import:R0125-6.3")
      (libsource (lib "eagle-import") (part "R1/8-6MM"))
    )
    (comp (ref "R17")
      (value "R1/8-6MM")
      (footprint "eagle-import:R0125-6.3")
      (libsource (lib "eagle-import") (part "R1/8-6MM"))
    )
    (comp (ref "R18")
      (value "R1/8-6MM")
      (footprint "eagle-import:R0125-6.3")
      (libsource (lib "eagle-import") (part "R1/8-6MM"))
    )
    (comp (ref "R19")
      (value "R1/8-6MM")
      (footprint "eagle-import:R0125-6.3")
      (libsource (lib "eagle-import") (part "R1/8-6MM"))
    )
    (comp (ref "R20")
      (value "R1/8-6MM")
      (footprint "eagle-import:R0125-6.3")
      (libsource (lib "eagle-import") (part "R1/8-6MM"))
    )
    (comp (ref "R21")
      (value "R1/8-6MM")
      (footprint "eagle-import:R0125-6.3")
      (libsource (lib "eagle-import") (part "R1/8-6MM"))
    )
    (comp (ref "R22")
      (value "R1/8-6MM")
      (footprint "eagle-import:R0125-6.3")
      (libsource (lib "eagle-import") (part "R1/8-6MM"))
    )
    (comp (ref "R23")
      (value "R1/8-6MM")
      (footprint "eagle-import:R0125-6.3")
      (libsource (lib "eagle-import") (part "R1/8-6MM"))
    )
    (comp (ref "R24")
      (value "R1/8-6MM")
      (footprint "eagle-import:R0125-6.3")
      (libsource (lib "eagle-import") (part "R1/8-6MM"))
    )
    (comp (ref "R25")
      (value "R1/8-6MM")
      (footprint "eagle-import:R0125-6.3")
      (libsource (lib "eagle-import") (part "R1/8-6MM"))
    )
    (comp (ref "R26")
      (value "R1/8-6MM")
      (footprint "eagle-import:R0125-6.3")
      (libsource (lib "eagle-import") (part "R1/8-6MM"))
    )
    (comp (ref "R27")
      (value "R1/8-6MM")
      (footprint "eagle-import:R0125-6.3")
      (libsource (lib "eagle-import") (part "R1/8-6MM"))
    )
    (comp (ref "R28")
      (value "R1/8-6MM")
      (footprint "eagle-import:R0125-6.3")
      (libsource (lib "eagle-import") (part "R1/8-6MM"))
    )
    (comp (ref "R29")
      (value "R1/8-6MM")
      (footprint "eagle-import:R0125-6.3")
      (libsource (lib "eagle-import") (part "R1/8-6MM"))
    )
    (comp (ref "R30")
      (value "R1/8-6MM")
      (footprint "eagle-import:R0125-6.3")
      (libsource (lib "eagle-import") (part "R1/8-6MM"))
    )
    (comp (ref "R31")
      (value "R1/8-6MM")
      (footprint "eagle-import:R0125-6.3")
      (libsource (lib "eagle-import") (part "R1/8-6MM"))
    )
    (comp (ref "R32")
      (value "R1/8-6MM")
      (footprint "eagle-import:R0125-6.3")
      (libsource (lib "eagle-import") (part "R1/8-6MM"))
    )
    (comp (ref "VR1")
      (value "SMPS")
      (footprint "eagle-import:BUCK1722")
      (libsource (lib "eagle-import") (part "SMPS"))
    )
  )
  (nets
    (net (code "1") (name "CARDENABLE") (class "Default")
      (node (ref "CN34") (pin "P$4") (pinfunction "4_P$4") (pintype "bidirectional"))
      (node (ref "D182") (pin "C") (pinfunction "C_C") (pintype "passive"))
      (node (ref "D183") (pin "C") (pinfunction "C_C") (pintype "passive"))
      (node (ref "D184") (pin "C") (pinfunction "C_C") (pintype "passive"))
      (node (ref "D185") (pin "C") (pinfunction "C_C") (pintype "passive"))
      (node (ref "D186") (pin "C") (pinfunction "C_C") (pintype "passive"))
      (node (ref "D187") (pin "C") (pinfunction "C_C") (pintype "passive"))
      (node (ref "D188") (pin "C") (pinfunction "C_C") (pintype "passive"))
      (node (ref "D189") (pin "C") (pinfunction "C_C") (pintype "passive"))
      (node (ref "D190") (pin "C") (pinfunction "C_C") (pintype "passive"))
      (node (ref "D191") (pin "C") (pinfunction "C_C") (pintype "passive"))
      (node (ref "D192") (pin "C") (pinfunction "C_C") (pintype "passive"))
      (node (ref "D193") (pin "C") (pinfunction "C_C") (pintype "passive"))
      (node (ref "D194") (pin "C") (pinfunction "C_C") (pintype "passive"))
      (node (ref "D195") (pin "C") (pinfunction "C_C") (pintype "passive"))
      (node (ref "D196") (pin "C") (pinfunction "C_C") (pintype "passive"))
      (node (ref "D197") (pin "C") (pinfunction "C_C") (pintype "passive"))
    )
    (net (code "2") (name "DB0") (class "Default")
      (node (ref "CN0") (pin "P$1") (pinfunction "1_P$1") (pintype "bidirectional"))
      (node (ref "D1") (pin "A") (pinfunction "A_A") (pintype "passive"))
      (node (ref "D100") (pin "A") (pinfunction "A_A") (pintype "passive"))
      (node (ref "D111") (pin "A") (pinfunction "A_A") (pintype "passive"))
      (node (ref "D12") (pin "A") (pinfunction "A_A") (pintype "passive"))
      (node (ref "D122") (pin "A") (pinfunction "A_A") (pintype "passive"))
      (node (ref "D133") (pin "A") (pinfunction "A_A") (pintype "passive"))
      (node (ref "D144") (pin "A") (pinfunction "A_A") (pintype "passive"))
      (node (ref "D155") (pin "A") (pinfunction "A_A") (pintype "passive"))
      (node (ref "D166") (pin "A") (pinfunction "A_A") (pintype "passive"))
      (node (ref "D23") (pin "A") (pinfunction "A_A") (pintype "passive"))
      (node (ref "D34") (pin "A") (pinfunction "A_A") (pintype "passive"))
      (node (ref "D45") (pin "A") (pinfunction "A_A") (pintype "passive"))
      (node (ref "D56") (pin "A") (pinfunction "A_A") (pintype "passive"))
      (node (ref "D67") (pin "A") (pinfunction "A_A") (pintype "passive"))
      (node (ref "D78") (pin "A") (pinfunction "A_A") (pintype "passive"))
      (node (ref "D89") (pin "A") (pinfunction "A_A") (pintype "passive"))
    )
    (net (code "3") (name "DB1") (class "Default")
      (node (ref "CN0") (pin "P$2") (pinfunction "2_P$2") (pintype "bidirectional"))
      (node (ref "D101") (pin "A") (pinfunction "A_A") (pintype "passive"))
      (node (ref "D112") (pin "A") (pinfunction "A_A") (pintype "passive"))
      (node (ref "D123") (pin "A") (pinfunction "A_A") (pintype "passive"))
      (node (ref "D13") (pin "A") (pinfunction "A_A") (pintype "passive"))
      (node (ref "D134") (pin "A") (pinfunction "A_A") (pintype "passive"))
      (node (ref "D145") (pin "A") (pinfunction "A_A") (pintype "passive"))
      (node (ref "D156") (pin "A") (pinfunction "A_A") (pintype "passive"))
      (node (ref "D167") (pin "A") (pinfunction "A_A") (pintype "passive"))
      (node (ref "D2") (pin "A") (pinfunction "A_A") (pintype "passive"))
      (node (ref "D24") (pin "A") (pinfunction "A_A") (pintype "passive"))
      (node (ref "D35") (pin "A") (pinfunction "A_A") (pintype "passive"))
      (node (ref "D46") (pin "A") (pinfunction "A_A") (pintype "passive"))
      (node (ref "D57") (pin "A") (pinfunction "A_A") (pintype "passive"))
      (node (ref "D68") (pin "A") (pinfunction "A_A") (pintype "passive"))
      (node (ref "D79") (pin "A") (pinfunction "A_A") (pintype "passive"))
      (node (ref "D90") (pin "A") (pinfunction "A_A") (pintype "passive"))
    )
    (net (code "4") (name "DB2") (class "Default")
      (node (ref "CN0") (pin "P$3") (pinfunction "3_P$3") (pintype "bidirectional"))
      (node (ref "D102") (pin "A") (pinfunction "A_A") (pintype "passive"))
      (node (ref "D113") (pin "A") (pinfunction "A_A") (pintype "passive"))
      (node (ref "D124") (pin "A") (pinfunction "A_A") (pintype "passive"))
      (node (ref "D135") (pin "A") (pinfunction "A_A") (pintype "passive"))
      (node (ref "D14") (pin "A") (pinfunction "A_A") (pintype "passive"))
      (node (ref "D146") (pin "A") (pinfunction "A_A") (pintype "passive"))
      (node (ref "D157") (pin "A") (pinfunction "A_A") (pintype "passive"))
      (node (ref "D168") (pin "A") (pinfunction "A_A") (pintype "passive"))
      (node (ref "D25") (pin "A") (pinfunction "A_A") (pintype "passive"))
      (node (ref "D3") (pin "A") (pinfunction "A_A") (pintype "passive"))
      (node (ref "D36") (pin "A") (pinfunction "A_A") (pintype "passive"))
      (node (ref "D47") (pin "A") (pinfunction "A_A") (pintype "passive"))
      (node (ref "D58") (pin "A") (pinfunction "A_A") (pintype "passive"))
      (node (ref "D69") (pin "A") (pinfunction "A_A") (pintype "passive"))
      (node (ref "D80") (pin "A") (pinfunction "A_A") (pintype "passive"))
      (node (ref "D91") (pin "A") (pinfunction "A_A") (pintype "passive"))
    )
    (net (code "5") (name "DB3") (class "Default")
      (node (ref "CN0") (pin "P$4") (pinfunction "4_P$4") (pintype "bidirectional"))
      (node (ref "D103") (pin "A") (pinfunction "A_A") (pintype "passive"))
      (node (ref "D114") (pin "A") (pinfunction "A_A") (pintype "passive"))
      (node (ref "D125") (pin "A") (pinfunction "A_A") (pintype "passive"))
      (node (ref "D136") (pin "A") (pinfunction "A_A") (pintype "passive"))
      (node (ref "D147") (pin "A") (pinfunction "A_A") (pintype "passive"))
      (node (ref "D15") (pin "A") (pinfunction "A_A") (pintype "passive"))
      (node (ref "D158") (pin "A") (pinfunction "A_A") (pintype "passive"))
      (node (ref "D169") (pin "A") (pinfunction "A_A") (pintype "passive"))
      (node (ref "D26") (pin "A") (pinfunction "A_A") (pintype "passive"))
      (node (ref "D37") (pin "A") (pinfunction "A_A") (pintype "passive"))
      (node (ref "D4") (pin "A") (pinfunction "A_A") (pintype "passive"))
      (node (ref "D48") (pin "A") (pinfunction "A_A") (pintype "passive"))
      (node (ref "D59") (pin "A") (pinfunction "A_A") (pintype "passive"))
      (node (ref "D70") (pin "A") (pinfunction "A_A") (pintype "passive"))
      (node (ref "D81") (pin "A") (pinfunction "A_A") (pintype "passive"))
      (node (ref "D92") (pin "A") (pinfunction "A_A") (pintype "passive"))
    )
    (net (code "6") (name "DB4") (class "Default")
      (node (ref "CN0") (pin "P$5") (pinfunction "5_P$5") (pintype "bidirectional"))
      (node (ref "D104") (pin "A") (pinfunction "A_A") (pintype "passive"))
      (node (ref "D115") (pin "A") (pinfunction "A_A") (pintype "passive"))
      (node (ref "D126") (pin "A") (pinfunction "A_A") (pintype "passive"))
      (node (ref "D137") (pin "A") (pinfunction "A_A") (pintype "passive"))
      (node (ref "D148") (pin "A") (pinfunction "A_A") (pintype "passive"))
      (node (ref "D159") (pin "A") (pinfunction "A_A") (pintype "passive"))
      (node (ref "D16") (pin "A") (pinfunction "A_A") (pintype "passive"))
      (node (ref "D170") (pin "A") (pinfunction "A_A") (pintype "passive"))
      (node (ref "D27") (pin "A") (pinfunction "A_A") (pintype "passive"))
      (node (ref "D38") (pin "A") (pinfunction "A_A") (pintype "passive"))
      (node (ref "D49") (pin "A") (pinfunction "A_A") (pintype "passive"))
      (node (ref "D5") (pin "A") (pinfunction "A_A") (pintype "passive"))
      (node (ref "D60") (pin "A") (pinfunction "A_A") (pintype "passive"))
      (node (ref "D71") (pin "A") (pinfunction "A_A") (pintype "passive"))
      (node (ref "D82") (pin "A") (pinfunction "A_A") (pintype "passive"))
      (node (ref "D93") (pin "A") (pinfunction "A_A") (pintype "passive"))
    )
    (net (code "7") (name "DB5") (class "Default")
      (node (ref "CN0") (pin "P$6") (pinfunction "6_P$6") (pintype "bidirectional"))
      (node (ref "D105") (pin "A") (pinfunction "A_A") (pintype "passive"))
      (node (ref "D116") (pin "A") (pinfunction "A_A") (pintype "passive"))
      (node (ref "D127") (pin "A") (pinfunction "A_A") (pintype "passive"))
      (node (ref "D138") (pin "A") (pinfunction "A_A") (pintype "passive"))
      (node (ref "D149") (pin "A") (pinfunction "A_A") (pintype "passive"))
      (node (ref "D160") (pin "A") (pinfunction "A_A") (pintype "passive"))
      (node (ref "D17") (pin "A") (pinfunction "A_A") (pintype "passive"))
      (node (ref "D171") (pin "A") (pinfunction "A_A") (pintype "passive"))
      (node (ref "D28") (pin "A") (pinfunction "A_A") (pintype "passive"))
      (node (ref "D39") (pin "A") (pinfunction "A_A") (pintype "passive"))
      (node (ref "D50") (pin "A") (pinfunction "A_A") (pintype "passive"))
      (node (ref "D6") (pin "A") (pinfunction "A_A") (pintype "passive"))
      (node (ref "D61") (pin "A") (pinfunction "A_A") (pintype "passive"))
      (node (ref "D72") (pin "A") (pinfunction "A_A") (pintype "passive"))
      (node (ref "D83") (pin "A") (pinfunction "A_A") (pintype "passive"))
      (node (ref "D94") (pin "A") (pinfunction "A_A") (pintype "passive"))
    )
    (net (code "8") (name "DB6") (class "Default")
      (node (ref "CN0") (pin "P$7") (pinfunction "7_P$7") (pintype "bidirectional"))
      (node (ref "D106") (pin "A") (pinfunction "A_A") (pintype "passive"))
      (node (ref "D117") (pin "A") (pinfunction "A_A") (pintype "passive"))
      (node (ref "D128") (pin "A") (pinfunction "A_A") (pintype "passive"))
      (node (ref "D139") (pin "A") (pinfunction "A_A") (pintype "passive"))
      (node (ref "D150") (pin "A") (pinfunction "A_A") (pintype "passive"))
      (node (ref "D161") (pin "A") (pinfunction "A_A") (pintype "passive"))
      (node (ref "D172") (pin "A") (pinfunction "A_A") (pintype "passive"))
      (node (ref "D18") (pin "A") (pinfunction "A_A") (pintype "passive"))
      (node (ref "D29") (pin "A") (pinfunction "A_A") (pintype "passive"))
      (node (ref "D40") (pin "A") (pinfunction "A_A") (pintype "passive"))
      (node (ref "D51") (pin "A") (pinfunction "A_A") (pintype "passive"))
      (node (ref "D62") (pin "A") (pinfunction "A_A") (pintype "passive"))
      (node (ref "D7") (pin "A") (pinfunction "A_A") (pintype "passive"))
      (node (ref "D73") (pin "A") (pinfunction "A_A") (pintype "passive"))
      (node (ref "D84") (pin "A") (pinfunction "A_A") (pintype "passive"))
      (node (ref "D95") (pin "A") (pinfunction "A_A") (pintype "passive"))
    )
    (net (code "9") (name "DB7") (class "Default")
      (node (ref "CN0") (pin "P$8") (pinfunction "8_P$8") (pintype "bidirectional"))
      (node (ref "D107") (pin "A") (pinfunction "A_A") (pintype "passive"))
      (node (ref "D118") (pin "A") (pinfunction "A_A") (pintype "passive"))
      (node (ref "D129") (pin "A") (pinfunction "A_A") (pintype "passive"))
      (node (ref "D140") (pin "A") (pinfunction "A_A") (pintype "passive"))
      (node (ref "D151") (pin "A") (pinfunction "A_A") (pintype "passive"))
      (node (ref "D162") (pin "A") (pinfunction "A_A") (pintype "passive"))
      (node (ref "D173") (pin "A") (pinfunction "A_A") (pintype "passive"))
      (node (ref "D19") (pin "A") (pinfunction "A_A") (pintype "passive"))
      (node (ref "D30") (pin "A") (pinfunction "A_A") (pintype "passive"))
      (node (ref "D41") (pin "A") (pinfunction "A_A") (pintype "passive"))
      (node (ref "D52") (pin "A") (pinfunction "A_A") (pintype "passive"))
      (node (ref "D63") (pin "A") (pinfunction "A_A") (pintype "passive"))
      (node (ref "D74") (pin "A") (pinfunction "A_A") (pintype "passive"))
      (node (ref "D8") (pin "A") (pinfunction "A_A") (pintype "passive"))
      (node (ref "D85") (pin "A") (pinfunction "A_A") (pintype "passive"))
      (node (ref "D96") (pin "A") (pinfunction "A_A") (pintype "passive"))
    )
    (net (code "10") (name "DB8") (class "Default")
      (node (ref "CN0") (pin "P$9") (pinfunction "9_P$9") (pintype "bidirectional"))
      (node (ref "D108") (pin "A") (pinfunction "A_A") (pintype "passive"))
      (node (ref "D119") (pin "A") (pinfunction "A_A") (pintype "passive"))
      (node (ref "D130") (pin "A") (pinfunction "A_A") (pintype "passive"))
      (node (ref "D141") (pin "A") (pinfunction "A_A") (pintype "passive"))
      (node (ref "D152") (pin "A") (pinfunction "A_A") (pintype "passive"))
      (node (ref "D163") (pin "A") (pinfunction "A_A") (pintype "passive"))
      (node (ref "D174") (pin "A") (pinfunction "A_A") (pintype "passive"))
      (node (ref "D20") (pin "A") (pinfunction "A_A") (pintype "passive"))
      (node (ref "D31") (pin "A") (pinfunction "A_A") (pintype "passive"))
      (node (ref "D42") (pin "A") (pinfunction "A_A") (pintype "passive"))
      (node (ref "D53") (pin "A") (pinfunction "A_A") (pintype "passive"))
      (node (ref "D64") (pin "A") (pinfunction "A_A") (pintype "passive"))
      (node (ref "D75") (pin "A") (pinfunction "A_A") (pintype "passive"))
      (node (ref "D86") (pin "A") (pinfunction "A_A") (pintype "passive"))
      (node (ref "D9") (pin "A") (pinfunction "A_A") (pintype "passive"))
      (node (ref "D97") (pin "A") (pinfunction "A_A") (pintype "passive"))
    )
    (net (code "11") (name "DB9") (class "Default")
      (node (ref "CN0") (pin "P$10") (pinfunction "10_P$10") (pintype "bidirectional"))
      (node (ref "D10") (pin "A") (pinfunction "A_A") (pintype "passive"))
      (node (ref "D109") (pin "A") (pinfunction "A_A") (pintype "passive"))
      (node (ref "D120") (pin "A") (pinfunction "A_A") (pintype "passive"))
      (node (ref "D131") (pin "A") (pinfunction "A_A") (pintype "passive"))
      (node (ref "D142") (pin "A") (pinfunction "A_A") (pintype "passive"))
      (node (ref "D153") (pin "A") (pinfunction "A_A") (pintype "passive"))
      (node (ref "D164") (pin "A") (pinfunction "A_A") (pintype "passive"))
      (node (ref "D175") (pin "A") (pinfunction "A_A") (pintype "passive"))
      (node (ref "D21") (pin "A") (pinfunction "A_A") (pintype "passive"))
      (node (ref "D32") (pin "A") (pinfunction "A_A") (pintype "passive"))
      (node (ref "D43") (pin "A") (pinfunction "A_A") (pintype "passive"))
      (node (ref "D54") (pin "A") (pinfunction "A_A") (pintype "passive"))
      (node (ref "D65") (pin "A") (pinfunction "A_A") (pintype "passive"))
      (node (ref "D76") (pin "A") (pinfunction "A_A") (pintype "passive"))
      (node (ref "D87") (pin "A") (pinfunction "A_A") (pintype "passive"))
      (node (ref "D98") (pin "A") (pinfunction "A_A") (pintype "passive"))
    )
    (net (code "12") (name "DB10") (class "Default")
      (node (ref "CN0") (pin "P$11") (pinfunction "11_P$11") (pintype "bidirectional"))
      (node (ref "D11") (pin "A") (pinfunction "A_A") (pintype "passive"))
      (node (ref "D110") (pin "A") (pinfunction "A_A") (pintype "passive"))
      (node (ref "D121") (pin "A") (pinfunction "A_A") (pintype "passive"))
      (node (ref "D132") (pin "A") (pinfunction "A_A") (pintype "passive"))
      (node (ref "D143") (pin "A") (pinfunction "A_A") (pintype "passive"))
      (node (ref "D154") (pin "A") (pinfunction "A_A") (pintype "passive"))
      (node (ref "D165") (pin "A") (pinfunction "A_A") (pintype "passive"))
      (node (ref "D176") (pin "A") (pinfunction "A_A") (pintype "passive"))
      (node (ref "D22") (pin "A") (pinfunction "A_A") (pintype "passive"))
      (node (ref "D33") (pin "A") (pinfunction "A_A") (pintype "passive"))
      (node (ref "D44") (pin "A") (pinfunction "A_A") (pintype "passive"))
      (node (ref "D55") (pin "A") (pinfunction "A_A") (pintype "passive"))
      (node (ref "D66") (pin "A") (pinfunction "A_A") (pintype "passive"))
      (node (ref "D77") (pin "A") (pinfunction "A_A") (pintype "passive"))
      (node (ref "D88") (pin "A") (pinfunction "A_A") (pintype "passive"))
      (node (ref "D99") (pin "A") (pinfunction "A_A") (pintype "passive"))
    )
    (net (code "13") (name "GND") (class "Default")
      (node (ref "CN34") (pin "P$1") (pinfunction "1_P$1") (pintype "bidirectional"))
      (node (ref "CN34") (pin "P$2") (pinfunction "2_P$2") (pintype "bidirectional"))
      (node (ref "Q1") (pin "E") (pinfunction "E_E") (pintype "passive"))
      (node (ref "Q10") (pin "E") (pinfunction "E_E") (pintype "passive"))
      (node (ref "Q11") (pin "E") (pinfunction "E_E") (pintype "passive"))
      (node (ref "Q12") (pin "E") (pinfunction "E_E") (pintype "passive"))
      (node (ref "Q13") (pin "E") (pinfunction "E_E") (pintype "passive"))
      (node (ref "Q14") (pin "E") (pinfunction "E_E") (pintype "passive"))
      (node (ref "Q15") (pin "E") (pinfunction "E_E") (pintype "passive"))
      (node (ref "Q16") (pin "E") (pinfunction "E_E") (pintype "passive"))
      (node (ref "Q2") (pin "E") (pinfunction "E_E") (pintype "passive"))
      (node (ref "Q3") (pin "E") (pinfunction "E_E") (pintype "passive"))
      (node (ref "Q4") (pin "E") (pinfunction "E_E") (pintype "passive"))
      (node (ref "Q5") (pin "E") (pinfunction "E_E") (pintype "passive"))
      (node (ref "Q6") (pin "E") (pinfunction "E_E") (pintype "passive"))
      (node (ref "Q7") (pin "E") (pinfunction "E_E") (pintype "passive"))
      (node (ref "Q8") (pin "E") (pinfunction "E_E") (pintype "passive"))
      (node (ref "Q9") (pin "E") (pinfunction "E_E") (pintype "passive"))
      (node (ref "VR1") (pin "GND@1") (pinfunction "GND_GND@1") (pintype "power_in"))
      (node (ref "VR1") (pin "GND@2") (pinfunction "GND_GND@2") (pintype "power_in"))
      (node (ref "VR1") (pin "GND@3") (pinfunction "GND_GND@3") (pintype "power_in"))
      (node (ref "VR1") (pin "GND@4") (pinfunction "GND_GND@4") (pintype "power_in"))
    )
    (net (code "14") (name "Net-(CN1-1)") (class "Default")
      (node (ref "CN1") (pin "P$1") (pinfunction "1_P$1") (pintype "bidirectional"))
      (node (ref "D1") (pin "C") (pinfunction "C_C") (pintype "passive"))
    )
    (net (code "15") (name "Net-(CN1-2)") (class "Default")
      (node (ref "CN1") (pin "P$2") (pinfunction "2_P$2") (pintype "bidirectional"))
      (node (ref "D2") (pin "C") (pinfunction "C_C") (pintype "passive"))
    )
    (net (code "16") (name "Net-(CN1-3)") (class "Default")
      (node (ref "CN1") (pin "P$3") (pinfunction "3_P$3") (pintype "bidirectional"))
      (node (ref "D3") (pin "C") (pinfunction "C_C") (pintype "passive"))
    )
    (net (code "17") (name "Net-(CN1-4)") (class "Default")
      (node (ref "CN1") (pin "P$4") (pinfunction "4_P$4") (pintype "bidirectional"))
      (node (ref "D4") (pin "C") (pinfunction "C_C") (pintype "passive"))
    )
    (net (code "18") (name "Net-(CN1-5)") (class "Default")
      (node (ref "CN1") (pin "P$5") (pinfunction "5_P$5") (pintype "bidirectional"))
      (node (ref "D5") (pin "C") (pinfunction "C_C") (pintype "passive"))
    )
    (net (code "19") (name "Net-(CN1-6)") (class "Default")
      (node (ref "CN1") (pin "P$6") (pinfunction "6_P$6") (pintype "bidirectional"))
      (node (ref "D6") (pin "C") (pinfunction "C_C") (pintype "passive"))
    )
    (net (code "20") (name "Net-(CN1-7)") (class "Default")
      (node (ref "CN1") (pin "P$7") (pinfunction "7_P$7") (pintype "bidirectional"))
      (node (ref "D7") (pin "C") (pinfunction "C_C") (pintype "passive"))
    )
    (net (code "21") (name "Net-(CN1-8)") (class "Default")
      (node (ref "CN1") (pin "P$8") (pinfunction "8_P$8") (pintype "bidirectional"))
      (node (ref "D8") (pin "C") (pinfunction "C_C") (pintype "passive"))
    )
    (net (code "22") (name "Net-(CN1-9)") (class "Default")
      (node (ref "CN1") (pin "P$9") (pinfunction "9_P$9") (pintype "bidirectional"))
      (node (ref "D9") (pin "C") (pinfunction "C_C") (pintype "passive"))
    )
    (net (code "23") (name "Net-(CN1-10)") (class "Default")
      (node (ref "CN1") (pin "P$10") (pinfunction "10_P$10") (pintype "bidirectional"))
      (node (ref "D10") (pin "C") (pinfunction "C_C") (pintype "passive"))
    )
    (net (code "24") (name "Net-(CN1-11)") (class "Default")
      (node (ref "CN1") (pin "P$11") (pinfunction "11_P$11") (pintype "bidirectional"))
      (node (ref "D11") (pin "C") (pinfunction "C_C") (pintype "passive"))
    )
    (net (code "25") (name "Net-(CN3-1)") (class "Default")
      (node (ref "CN3") (pin "P$1") (pinfunction "1_P$1") (pintype "bidirectional"))
      (node (ref "D12") (pin "C") (pinfunction "C_C") (pintype "passive"))
    )
    (net (code "26") (name "Net-(CN3-2)") (class "Default")
      (node (ref "CN3") (pin "P$2") (pinfunction "2_P$2") (pintype "bidirectional"))
      (node (ref "D13") (pin "C") (pinfunction "C_C") (pintype "passive"))
    )
    (net (code "27") (name "Net-(CN3-3)") (class "Default")
      (node (ref "CN3") (pin "P$3") (pinfunction "3_P$3") (pintype "bidirectional"))
      (node (ref "D14") (pin "C") (pinfunction "C_C") (pintype "passive"))
    )
    (net (code "28") (name "Net-(CN3-4)") (class "Default")
      (node (ref "CN3") (pin "P$4") (pinfunction "4_P$4") (pintype "bidirectional"))
      (node (ref "D15") (pin "C") (pinfunction "C_C") (pintype "passive"))
    )
    (net (code "29") (name "Net-(CN3-5)") (class "Default")
      (node (ref "CN3") (pin "P$5") (pinfunction "5_P$5") (pintype "bidirectional"))
      (node (ref "D16") (pin "C") (pinfunction "C_C") (pintype "passive"))
    )
    (net (code "30") (name "Net-(CN3-6)") (class "Default")
      (node (ref "CN3") (pin "P$6") (pinfunction "6_P$6") (pintype "bidirectional"))
      (node (ref "D17") (pin "C") (pinfunction "C_C") (pintype "passive"))
    )
    (net (code "31") (name "Net-(CN3-7)") (class "Default")
      (node (ref "CN3") (pin "P$7") (pinfunction "7_P$7") (pintype "bidirectional"))
      (node (ref "D18") (pin "C") (pinfunction "C_C") (pintype "passive"))
    )
    (net (code "32") (name "Net-(CN3-8)") (class "Default")
      (node (ref "CN3") (pin "P$8") (pinfunction "8_P$8") (pintype "bidirectional"))
      (node (ref "D19") (pin "C") (pinfunction "C_C") (pintype "passive"))
    )
    (net (code "33") (name "Net-(CN3-9)") (class "Default")
      (node (ref "CN3") (pin "P$9") (pinfunction "9_P$9") (pintype "bidirectional"))
      (node (ref "D20") (pin "C") (pinfunction "C_C") (pintype "passive"))
    )
    (net (code "34") (name "Net-(CN3-10)") (class "Default")
      (node (ref "CN3") (pin "P$10") (pinfunction "10_P$10") (pintype "bidirectional"))
      (node (ref "D21") (pin "C") (pinfunction "C_C") (pintype "passive"))
    )
    (net (code "35") (name "Net-(CN3-11)") (class "Default")
      (node (ref "CN3") (pin "P$11") (pinfunction "11_P$11") (pintype "bidirectional"))
      (node (ref "D22") (pin "C") (pinfunction "C_C") (pintype "passive"))
    )
    (net (code "36") (name "Net-(CN5-1)") (class "Default")
      (node (ref "CN5") (pin "P$1") (pinfunction "1_P$1") (pintype "bidirectional"))
      (node (ref "D23") (pin "C") (pinfunction "C_C") (pintype "passive"))
    )
    (net (code "37") (name "Net-(CN5-2)") (class "Default")
      (node (ref "CN5") (pin "P$2") (pinfunction "2_P$2") (pintype "bidirectional"))
      (node (ref "D24") (pin "C") (pinfunction "C_C") (pintype "passive"))
    )
    (net (code "38") (name "Net-(CN5-3)") (class "Default")
      (node (ref "CN5") (pin "P$3") (pinfunction "3_P$3") (pintype "bidirectional"))
      (node (ref "D25") (pin "C") (pinfunction "C_C") (pintype "passive"))
    )
    (net (code "39") (name "Net-(CN5-4)") (class "Default")
      (node (ref "CN5") (pin "P$4") (pinfunction "4_P$4") (pintype "bidirectional"))
      (node (ref "D26") (pin "C") (pinfunction "C_C") (pintype "passive"))
    )
    (net (code "40") (name "Net-(CN5-5)") (class "Default")
      (node (ref "CN5") (pin "P$5") (pinfunction "5_P$5") (pintype "bidirectional"))
      (node (ref "D27") (pin "C") (pinfunction "C_C") (pintype "passive"))
    )
    (net (code "41") (name "Net-(CN5-6)") (class "Default")
      (node (ref "CN5") (pin "P$6") (pinfunction "6_P$6") (pintype "bidirectional"))
      (node (ref "D28") (pin "C") (pinfunction "C_C") (pintype "passive"))
    )
    (net (code "42") (name "Net-(CN5-7)") (class "Default")
      (node (ref "CN5") (pin "P$7") (pinfunction "7_P$7") (pintype "bidirectional"))
      (node (ref "D29") (pin "C") (pinfunction "C_C") (pintype "passive"))
    )
    (net (code "43") (name "Net-(CN5-8)") (class "Default")
      (node (ref "CN5") (pin "P$8") (pinfunction "8_P$8") (pintype "bidirectional"))
      (node (ref "D30") (pin "C") (pinfunction "C_C") (pintype "passive"))
    )
    (net (code "44") (name "Net-(CN5-9)") (class "Default")
      (node (ref "CN5") (pin "P$9") (pinfunction "9_P$9") (pintype "bidirectional"))
      (node (ref "D31") (pin "C") (pinfunction "C_C") (pintype "passive"))
    )
    (net (code "45") (name "Net-(CN5-10)") (class "Default")
      (node (ref "CN5") (pin "P$10") (pinfunction "10_P$10") (pintype "bidirectional"))
      (node (ref "D32") (pin "C") (pinfunction "C_C") (pintype "passive"))
    )
    (net (code "46") (name "Net-(CN5-11)") (class "Default")
      (node (ref "CN5") (pin "P$11") (pinfunction "11_P$11") (pintype "bidirectional"))
      (node (ref "D33") (pin "C") (pinfunction "C_C") (pintype "passive"))
    )
    (net (code "47") (name "Net-(CN7-1)") (class "Default")
      (node (ref "CN7") (pin "P$1") (pinfunction "1_P$1") (pintype "bidirectional"))
      (node (ref "D45") (pin "C") (pinfunction "C_C") (pintype "passive"))
    )
    (net (code "48") (name "Net-(CN7-2)") (class "Default")
      (node (ref "CN7") (pin "P$2") (pinfunction "2_P$2") (pintype "bidirectional"))
      (node (ref "D46") (pin "C") (pinfunction "C_C") (pintype "passive"))
    )
    (net (code "49") (name "Net-(CN7-3)") (class "Default")
      (node (ref "CN7") (pin "P$3") (pinfunction "3_P$3") (pintype "bidirectional"))
      (node (ref "D47") (pin "C") (pinfunction "C_C") (pintype "passive"))
    )
    (net (code "50") (name "Net-(CN7-4)") (class "Default")
      (node (ref "CN7") (pin "P$4") (pinfunction "4_P$4") (pintype "bidirectional"))
      (node (ref "D48") (pin "C") (pinfunction "C_C") (pintype "passive"))
    )
    (net (code "51") (name "Net-(CN7-5)") (class "Default")
      (node (ref "CN7") (pin "P$5") (pinfunction "5_P$5") (pintype "bidirectional"))
      (node (ref "D49") (pin "C") (pinfunction "C_C") (pintype "passive"))
    )
    (net (code "52") (name "Net-(CN7-6)") (class "Default")
      (node (ref "CN7") (pin "P$6") (pinfunction "6_P$6") (pintype "bidirectional"))
      (node (ref "D50") (pin "C") (pinfunction "C_C") (pintype "passive"))
    )
    (net (code "53") (name "Net-(CN7-7)") (class "Default")
      (node (ref "CN7") (pin "P$7") (pinfunction "7_P$7") (pintype "bidirectional"))
      (node (ref "D51") (pin "C") (pinfunction "C_C") (pintype "passive"))
    )
    (net (code "54") (name "Net-(CN7-8)") (class "Default")
      (node (ref "CN7") (pin "P$8") (pinfunction "8_P$8") (pintype "bidirectional"))
      (node (ref "D52") (pin "C") (pinfunction "C_C") (pintype "passive"))
    )
    (net (code "55") (name "Net-(CN7-9)") (class "Default")
      (node (ref "CN7") (pin "P$9") (pinfunction "9_P$9") (pintype "bidirectional"))
      (node (ref "D53") (pin "C") (pinfunction "C_C") (pintype "passive"))
    )
    (net (code "56") (name "Net-(CN7-10)") (class "Default")
      (node (ref "CN7") (pin "P$10") (pinfunction "10_P$10") (pintype "bidirectional"))
      (node (ref "D54") (pin "C") (pinfunction "C_C") (pintype "passive"))
    )
    (net (code "57") (name "Net-(CN7-11)") (class "Default")
      (node (ref "CN7") (pin "P$11") (pinfunction "11_P$11") (pintype "bidirectional"))
      (node (ref "D55") (pin "C") (pinfunction "C_C") (pintype "passive"))
    )
    (net (code "58") (name "Net-(CN8-1)") (class "Default")
      (node (ref "CN8") (pin "P$1") (pinfunction "1_P$1") (pintype "bidirectional"))
      (node (ref "D34") (pin "C") (pinfunction "C_C") (pintype "passive"))
    )
    (net (code "59") (name "Net-(CN8-2)") (class "Default")
      (node (ref "CN8") (pin "P$2") (pinfunction "2_P$2") (pintype "bidirectional"))
      (node (ref "D35") (pin "C") (pinfunction "C_C") (pintype "passive"))
    )
    (net (code "60") (name "Net-(CN8-3)") (class "Default")
      (node (ref "CN8") (pin "P$3") (pinfunction "3_P$3") (pintype "bidirectional"))
      (node (ref "D36") (pin "C") (pinfunction "C_C") (pintype "passive"))
    )
    (net (code "61") (name "Net-(CN8-4)") (class "Default")
      (node (ref "CN8") (pin "P$4") (pinfunction "4_P$4") (pintype "bidirectional"))
      (node (ref "D37") (pin "C") (pinfunction "C_C") (pintype "passive"))
    )
    (net (code "62") (name "Net-(CN8-5)") (class "Default")
      (node (ref "CN8") (pin "P$5") (pinfunction "5_P$5") (pintype "bidirectional"))
      (node (ref "D38") (pin "C") (pinfunction "C_C") (pintype "passive"))
    )
    (net (code "63") (name "Net-(CN8-6)") (class "Default")
      (node (ref "CN8") (pin "P$6") (pinfunction "6_P$6") (pintype "bidirectional"))
      (node (ref "D39") (pin "C") (pinfunction "C_C") (pintype "passive"))
    )
    (net (code "64") (name "Net-(CN8-7)") (class "Default")
      (node (ref "CN8") (pin "P$7") (pinfunction "7_P$7") (pintype "bidirectional"))
      (node (ref "D40") (pin "C") (pinfunction "C_C") (pintype "passive"))
    )
    (net (code "65") (name "Net-(CN8-8)") (class "Default")
      (node (ref "CN8") (pin "P$8") (pinfunction "8_P$8") (pintype "bidirectional"))
      (node (ref "D41") (pin "C") (pinfunction "C_C") (pintype "passive"))
    )
    (net (code "66") (name "Net-(CN8-9)") (class "Default")
      (node (ref "CN8") (pin "P$9") (pinfunction "9_P$9") (pintype "bidirectional"))
      (node (ref "D42") (pin "C") (pinfunction "C_C") (pintype "passive"))
    )
    (net (code "67") (name "Net-(CN8-10)") (class "Default")
      (node (ref "CN8") (pin "P$10") (pinfunction "10_P$10") (pintype "bidirectional"))
      (node (ref "D43") (pin "C") (pinfunction "C_C") (pintype "passive"))
    )
    (net (code "68") (name "Net-(CN8-11)") (class "Default")
      (node (ref "CN8") (pin "P$11") (pinfunction "11_P$11") (pintype "bidirectional"))
      (node (ref "D44") (pin "C") (pinfunction "C_C") (pintype "passive"))
    )
    (net (code "69") (name "Net-(CN11-1)") (class "Default")
      (node (ref "CN11") (pin "P$1") (pinfunction "1_P$1") (pintype "bidirectional"))
      (node (ref "D89") (pin "C") (pinfunction "C_C") (pintype "passive"))
    )
    (net (code "70") (name "Net-(CN11-2)") (class "Default")
      (node (ref "CN11") (pin "P$2") (pinfunction "2_P$2") (pintype "bidirectional"))
      (node (ref "D90") (pin "C") (pinfunction "C_C") (pintype "passive"))
    )
    (net (code "71") (name "Net-(CN11-3)") (class "Default")
      (node (ref "CN11") (pin "P$3") (pinfunction "3_P$3") (pintype "bidirectional"))
      (node (ref "D91") (pin "C") (pinfunction "C_C") (pintype "passive"))
    )
    (net (code "72") (name "Net-(CN11-4)") (class "Default")
      (node (ref "CN11") (pin "P$4") (pinfunction "4_P$4") (pintype "bidirectional"))
      (node (ref "D92") (pin "C") (pinfunction "C_C") (pintype "passive"))
    )
    (net (code "73") (name "Net-(CN11-5)") (class "Default")
      (node (ref "CN11") (pin "P$5") (pinfunction "5_P$5") (pintype "bidirectional"))
      (node (ref "D93") (pin "C") (pinfunction "C_C") (pintype "passive"))
    )
    (net (code "74") (name "Net-(CN11-6)") (class "Default")
      (node (ref "CN11") (pin "P$6") (pinfunction "6_P$6") (pintype "bidirectional"))
      (node (ref "D94") (pin "C") (pinfunction "C_C") (pintype "passive"))
    )
    (net (code "75") (name "Net-(CN11-7)") (class "Default")
      (node (ref "CN11") (pin "P$7") (pinfunction "7_P$7") (pintype "bidirectional"))
      (node (ref "D95") (pin "C") (pinfunction "C_C") (pintype "passive"))
    )
    (net (code "76") (name "Net-(CN11-8)") (class "Default")
      (node (ref "CN11") (pin "P$8") (pinfunction "8_P$8") (pintype "bidirectional"))
      (node (ref "D96") (pin "C") (pinfunction "C_C") (pintype "passive"))
    )
    (net (code "77") (name "Net-(CN11-9)") (class "Default")
      (node (ref "CN11") (pin "P$9") (pinfunction "9_P$9") (pintype "bidirectional"))
      (node (ref "D97") (pin "C") (pinfunction "C_C") (pintype "passive"))
    )
    (net (code "78") (name "Net-(CN11-10)") (class "Default")
      (node (ref "CN11") (pin "P$10") (pinfunction "10_P$10") (pintype "bidirectional"))
      (node (ref "D98") (pin "C") (pinfunction "C_C") (pintype "passive"))
    )
    (net (code "79") (name "Net-(CN11-11)") (class "Default")
      (node (ref "CN11") (pin "P$11") (pinfunction "11_P$11") (pintype "bidirectional"))
      (node (ref "D99") (pin "C") (pinfunction "C_C") (pintype "passive"))
    )
    (net (code "80") (name "Net-(CN12-1)") (class "Default")
      (node (ref "CN12") (pin "P$1") (pinfunction "1_P$1") (pintype "bidirectional"))
      (node (ref "D56") (pin "C") (pinfunction "C_C") (pintype "passive"))
    )
    (net (code "81") (name "Net-(CN12-2)") (class "Default")
      (node (ref "CN12") (pin "P$2") (pinfunction "2_P$2") (pintype "bidirectional"))
      (node (ref "D57") (pin "C") (pinfunction "C_C") (pintype "passive"))
    )
    (net (code "82") (name "Net-(CN12-3)") (class "Default")
      (node (ref "CN12") (pin "P$3") (pinfunction "3_P$3") (pintype "bidirectional"))
      (node (ref "D58") (pin "C") (pinfunction "C_C") (pintype "passive"))
    )
    (net (code "83") (name "Net-(CN12-4)") (class "Default")
      (node (ref "CN12") (pin "P$4") (pinfunction "4_P$4") (pintype "bidirectional"))
      (node (ref "D59") (pin "C") (pinfunction "C_C") (pintype "passive"))
    )
    (net (code "84") (name "Net-(CN12-5)") (class "Default")
      (node (ref "CN12") (pin "P$5") (pinfunction "5_P$5") (pintype "bidirectional"))
      (node (ref "D60") (pin "C") (pinfunction "C_C") (pintype "passive"))
    )
    (net (code "85") (name "Net-(CN12-6)") (class "Default")
      (node (ref "CN12") (pin "P$6") (pinfunction "6_P$6") (pintype "bidirectional"))
      (node (ref "D61") (pin "C") (pinfunction "C_C") (pintype "passive"))
    )
    (net (code "86") (name "Net-(CN12-7)") (class "Default")
      (node (ref "CN12") (pin "P$7") (pinfunction "7_P$7") (pintype "bidirectional"))
      (node (ref "D62") (pin "C") (pinfunction "C_C") (pintype "passive"))
    )
    (net (code "87") (name "Net-(CN12-8)") (class "Default")
      (node (ref "CN12") (pin "P$8") (pinfunction "8_P$8") (pintype "bidirectional"))
      (node (ref "D63") (pin "C") (pinfunction "C_C") (pintype "passive"))
    )
    (net (code "88") (name "Net-(CN12-9)") (class "Default")
      (node (ref "CN12") (pin "P$9") (pinfunction "9_P$9") (pintype "bidirectional"))
      (node (ref "D64") (pin "C") (pinfunction "C_C") (pintype "passive"))
    )
    (net (code "89") (name "Net-(CN12-10)") (class "Default")
      (node (ref "CN12") (pin "P$10") (pinfunction "10_P$10") (pintype "bidirectional"))
      (node (ref "D65") (pin "C") (pinfunction "C_C") (pintype "passive"))
    )
    (net (code "90") (name "Net-(CN12-11)") (class "Default")
      (node (ref "CN12") (pin "P$11") (pinfunction "11_P$11") (pintype "bidirectional"))
      (node (ref "D66") (pin "C") (pinfunction "C_C") (pintype "passive"))
    )
    (net (code "91") (name "Net-(CN14-1)") (class "Default")
      (node (ref "CN14") (pin "P$1") (pinfunction "1_P$1") (pintype "bidirectional"))
      (node (ref "D67") (pin "C") (pinfunction "C_C") (pintype "passive"))
    )
    (net (code "92") (name "Net-(CN14-2)") (class "Default")
      (node (ref "CN14") (pin "P$2") (pinfunction "2_P$2") (pintype "bidirectional"))
      (node (ref "D68") (pin "C") (pinfunction "C_C") (pintype "passive"))
    )
    (net (code "93") (name "Net-(CN14-3)") (class "Default")
      (node (ref "CN14") (pin "P$3") (pinfunction "3_P$3") (pintype "bidirectional"))
      (node (ref "D69") (pin "C") (pinfunction "C_C") (pintype "passive"))
    )
    (net (code "94") (name "Net-(CN14-4)") (class "Default")
      (node (ref "CN14") (pin "P$4") (pinfunction "4_P$4") (pintype "bidirectional"))
      (node (ref "D70") (pin "C") (pinfunction "C_C") (pintype "passive"))
    )
    (net (code "95") (name "Net-(CN14-5)") (class "Default")
      (node (ref "CN14") (pin "P$5") (pinfunction "5_P$5") (pintype "bidirectional"))
      (node (ref "D71") (pin "C") (pinfunction "C_C") (pintype "passive"))
    )
    (net (code "96") (name "Net-(CN14-6)") (class "Default")
      (node (ref "CN14") (pin "P$6") (pinfunction "6_P$6") (pintype "bidirectional"))
      (node (ref "D72") (pin "C") (pinfunction "C_C") (pintype "passive"))
    )
    (net (code "97") (name "Net-(CN14-7)") (class "Default")
      (node (ref "CN14") (pin "P$7") (pinfunction "7_P$7") (pintype "bidirectional"))
      (node (ref "D73") (pin "C") (pinfunction "C_C") (pintype "passive"))
    )
    (net (code "98") (name "Net-(CN14-8)") (class "Default")
      (node (ref "CN14") (pin "P$8") (pinfunction "8_P$8") (pintype "bidirectional"))
      (node (ref "D74") (pin "C") (pinfunction "C_C") (pintype "passive"))
    )
    (net (code "99") (name "Net-(CN14-9)") (class "Default")
      (node (ref "CN14") (pin "P$9") (pinfunction "9_P$9") (pintype "bidirectional"))
      (node (ref "D75") (pin "C") (pinfunction "C_C") (pintype "passive"))
    )
    (net (code "100") (name "Net-(CN14-10)") (class "Default")
      (node (ref "CN14") (pin "P$10") (pinfunction "10_P$10") (pintype "bidirectional"))
      (node (ref "D76") (pin "C") (pinfunction "C_C") (pintype "passive"))
    )
    (net (code "101") (name "Net-(CN14-11)") (class "Default")
      (node (ref "CN14") (pin "P$11") (pinfunction "11_P$11") (pintype "bidirectional"))
      (node (ref "D77") (pin "C") (pinfunction "C_C") (pintype "passive"))
    )
    (net (code "102") (name "Net-(CN16-1)") (class "Default")
      (node (ref "CN16") (pin "P$1") (pinfunction "1_P$1") (pintype "bidirectional"))
      (node (ref "D78") (pin "C") (pinfunction "C_C") (pintype "passive"))
    )
    (net (code "103") (name "Net-(CN16-2)") (class "Default")
      (node (ref "CN16") (pin "P$2") (pinfunction "2_P$2") (pintype "bidirectional"))
      (node (ref "D79") (pin "C") (pinfunction "C_C") (pintype "passive"))
    )
    (net (code "104") (name "Net-(CN16-3)") (class "Default")
      (node (ref "CN16") (pin "P$3") (pinfunction "3_P$3") (pintype "bidirectional"))
      (node (ref "D80") (pin "C") (pinfunction "C_C") (pintype "passive"))
    )
    (net (code "105") (name "Net-(CN16-4)") (class "Default")
      (node (ref "CN16") (pin "P$4") (pinfunction "4_P$4") (pintype "bidirectional"))
      (node (ref "D81") (pin "C") (pinfunction "C_C") (pintype "passive"))
    )
    (net (code "106") (name "Net-(CN16-5)") (class "Default")
      (node (ref "CN16") (pin "P$5") (pinfunction "5_P$5") (pintype "bidirectional"))
      (node (ref "D82") (pin "C") (pinfunction "C_C") (pintype "passive"))
    )
    (net (code "107") (name "Net-(CN16-6)") (class "Default")
      (node (ref "CN16") (pin "P$6") (pinfunction "6_P$6") (pintype "bidirectional"))
      (node (ref "D83") (pin "C") (pinfunction "C_C") (pintype "passive"))
    )
    (net (code "108") (name "Net-(CN16-7)") (class "Default")
      (node (ref "CN16") (pin "P$7") (pinfunction "7_P$7") (pintype "bidirectional"))
      (node (ref "D84") (pin "C") (pinfunction "C_C") (pintype "passive"))
    )
    (net (code "109") (name "Net-(CN16-8)") (class "Default")
      (node (ref "CN16") (pin "P$8") (pinfunction "8_P$8") (pintype "bidirectional"))
      (node (ref "D85") (pin "C") (pinfunction "C_C") (pintype "passive"))
    )
    (net (code "110") (name "Net-(CN16-9)") (class "Default")
      (node (ref "CN16") (pin "P$9") (pinfunction "9_P$9") (pintype "bidirectional"))
      (node (ref "D86") (pin "C") (pinfunction "C_C") (pintype "passive"))
    )
    (net (code "111") (name "Net-(CN16-10)") (class "Default")
      (node (ref "CN16") (pin "P$10") (pinfunction "10_P$10") (pintype "bidirectional"))
      (node (ref "D87") (pin "C") (pinfunction "C_C") (pintype "passive"))
    )
    (net (code "112") (name "Net-(CN16-11)") (class "Default")
      (node (ref "CN16") (pin "P$11") (pinfunction "11_P$11") (pintype "bidirectional"))
      (node (ref "D88") (pin "C") (pinfunction "C_C") (pintype "passive"))
    )
    (net (code "113") (name "Net-(CN19-1)") (class "Default")
      (node (ref "CN19") (pin "P$1") (pinfunction "1_P$1") (pintype "bidirectional"))
      (node (ref "D177") (pin "C") (pinfunction "C_C") (pintype "passive"))
    )
    (net (code "114") (name "Net-(CN19-2)") (class "Default")
      (node (ref "CN19") (pin "P$2") (pinfunction "2_P$2") (pintype "bidirectional"))
      (node (ref "D178") (pin "C") (pinfunction "C_C") (pintype "passive"))
    )
    (net (code "115") (name "Net-(CN19-3)") (class "Default")
      (node (ref "CN19") (pin "P$3") (pinfunction "3_P$3") (pintype "bidirectional"))
      (node (ref "D179") (pin "C") (pinfunction "C_C") (pintype "passive"))
    )
    (net (code "116") (name "Net-(CN19-4)") (class "Default")
      (node (ref "CN19") (pin "P$4") (pinfunction "4_P$4") (pintype "bidirectional"))
      (node (ref "D180") (pin "C") (pinfunction "C_C") (pintype "passive"))
    )
    (net (code "117") (name "Net-(CN19-5)") (class "Default")
      (node (ref "CN19") (pin "P$5") (pinfunction "5_P$5") (pintype "bidirectional"))
      (node (ref "D181") (pin "C") (pinfunction "C_C") (pintype "passive"))
    )
    (net (code "118") (name "Net-(CN19-6)") (class "Default")
      (node (ref "CN19") (pin "P$6") (pinfunction "6_P$6") (pintype "bidirectional"))
      (node (ref "D198") (pin "C") (pinfunction "C_C") (pintype "passive"))
    )
    (net (code "119") (name "Net-(CN19-7)") (class "Default")
      (node (ref "CN19") (pin "P$7") (pinfunction "7_P$7") (pintype "bidirectional"))
      (node (ref "D199") (pin "C") (pinfunction "C_C") (pintype "passive"))
    )
    (net (code "120") (name "Net-(CN19-8)") (class "Default")
      (node (ref "CN19") (pin "P$8") (pinfunction "8_P$8") (pintype "bidirectional"))
      (node (ref "D200") (pin "C") (pinfunction "C_C") (pintype "passive"))
    )
    (net (code "121") (name "Net-(CN19-9)") (class "Default")
      (node (ref "CN19") (pin "P$9") (pinfunction "9_P$9") (pintype "bidirectional"))
      (node (ref "D201") (pin "C") (pinfunction "C_C") (pintype "passive"))
    )
    (net (code "122") (name "Net-(CN19-10)") (class "Default")
      (node (ref "CN19") (pin "P$10") (pinfunction "10_P$10") (pintype "bidirectional"))
      (node (ref "D202") (pin "C") (pinfunction "C_C") (pintype "passive"))
    )
    (net (code "123") (name "Net-(CN19-11)") (class "Default")
      (node (ref "CN19") (pin "P$11") (pinfunction "11_P$11") (pintype "bidirectional"))
      (node (ref "D203") (pin "C") (pinfunction "C_C") (pintype "passive"))
    )
    (net (code "124") (name "Net-(CN19-12)") (class "Default")
      (node (ref "CN19") (pin "P$12") (pinfunction "12_P$12") (pintype "bidirectional"))
      (node (ref "D204") (pin "C") (pinfunction "C_C") (pintype "passive"))
    )
    (net (code "125") (name "Net-(CN19-13)") (class "Default")
      (node (ref "CN19") (pin "P$13") (pinfunction "13_P$13") (pintype "bidirectional"))
      (node (ref "D205") (pin "C") (pinfunction "C_C") (pintype "passive"))
    )
    (net (code "126") (name "Net-(CN19-14)") (class "Default")
      (node (ref "CN19") (pin "P$14") (pinfunction "14_P$14") (pintype "bidirectional"))
      (node (ref "D206") (pin "C") (pinfunction "C_C") (pintype "passive"))
    )
    (net (code "127") (name "Net-(CN19-15)") (class "Default")
      (node (ref "CN19") (pin "P$15") (pinfunction "15_P$15") (pintype "bidirectional"))
      (node (ref "D207") (pin "C") (pinfunction "C_C") (pintype "passive"))
    )
    (net (code "128") (name "Net-(CN19-16)") (class "Default")
      (node (ref "CN19") (pin "P$16") (pinfunction "16_P$16") (pintype "bidirectional"))
      (node (ref "D208") (pin "C") (pinfunction "C_C") (pintype "passive"))
    )
    (net (code "129") (name "Net-(CN20-1)") (class "Default")
      (node (ref "CN20") (pin "P$1") (pinfunction "1_P$1") (pintype "bidirectional"))
      (node (ref "D100") (pin "C") (pinfunction "C_C") (pintype "passive"))
    )
    (net (code "130") (name "Net-(CN20-2)") (class "Default")
      (node (ref "CN20") (pin "P$2") (pinfunction "2_P$2") (pintype "bidirectional"))
      (node (ref "D101") (pin "C") (pinfunction "C_C") (pintype "passive"))
    )
    (net (code "131") (name "Net-(CN20-3)") (class "Default")
      (node (ref "CN20") (pin "P$3") (pinfunction "3_P$3") (pintype "bidirectional"))
      (node (ref "D102") (pin "C") (pinfunction "C_C") (pintype "passive"))
    )
    (net (code "132") (name "Net-(CN20-4)") (class "Default")
      (node (ref "CN20") (pin "P$4") (pinfunction "4_P$4") (pintype "bidirectional"))
      (node (ref "D103") (pin "C") (pinfunction "C_C") (pintype "passive"))
    )
    (net (code "133") (name "Net-(CN20-5)") (class "Default")
      (node (ref "CN20") (pin "P$5") (pinfunction "5_P$5") (pintype "bidirectional"))
      (node (ref "D104") (pin "C") (pinfunction "C_C") (pintype "passive"))
    )
    (net (code "134") (name "Net-(CN20-6)") (class "Default")
      (node (ref "CN20") (pin "P$6") (pinfunction "6_P$6") (pintype "bidirectional"))
      (node (ref "D105") (pin "C") (pinfunction "C_C") (pintype "passive"))
    )
    (net (code "135") (name "Net-(CN20-7)") (class "Default")
      (node (ref "CN20") (pin "P$7") (pinfunction "7_P$7") (pintype "bidirectional"))
      (node (ref "D106") (pin "C") (pinfunction "C_C") (pintype "passive"))
    )
    (net (code "136") (name "Net-(CN20-8)") (class "Default")
      (node (ref "CN20") (pin "P$8") (pinfunction "8_P$8") (pintype "bidirectional"))
      (node (ref "D107") (pin "C") (pinfunction "C_C") (pintype "passive"))
    )
    (net (code "137") (name "Net-(CN20-9)") (class "Default")
      (node (ref "CN20") (pin "P$9") (pinfunction "9_P$9") (pintype "bidirectional"))
      (node (ref "D108") (pin "C") (pinfunction "C_C") (pintype "passive"))
    )
    (net (code "138") (name "Net-(CN20-10)") (class "Default")
      (node (ref "CN20") (pin "P$10") (pinfunction "10_P$10") (pintype "bidirectional"))
      (node (ref "D109") (pin "C") (pinfunction "C_C") (pintype "passive"))
    )
    (net (code "139") (name "Net-(CN20-11)") (class "Default")
      (node (ref "CN20") (pin "P$11") (pinfunction "11_P$11") (pintype "bidirectional"))
      (node (ref "D110") (pin "C") (pinfunction "C_C") (pintype "passive"))
    )
    (net (code "140") (name "Net-(CN22-1)") (class "Default")
      (node (ref "CN22") (pin "P$1") (pinfunction "1_P$1") (pintype "bidirectional"))
      (node (ref "D111") (pin "C") (pinfunction "C_C") (pintype "passive"))
    )
    (net (code "141") (name "Net-(CN22-2)") (class "Default")
      (node (ref "CN22") (pin "P$2") (pinfunction "2_P$2") (pintype "bidirectional"))
      (node (ref "D112") (pin "C") (pinfunction "C_C") (pintype "passive"))
    )
    (net (code "142") (name "Net-(CN22-3)") (class "Default")
      (node (ref "CN22") (pin "P$3") (pinfunction "3_P$3") (pintype "bidirectional"))
      (node (ref "D113") (pin "C") (pinfunction "C_C") (pintype "passive"))
    )
    (net (code "143") (name "Net-(CN22-4)") (class "Default")
      (node (ref "CN22") (pin "P$4") (pinfunction "4_P$4") (pintype "bidirectional"))
      (node (ref "D114") (pin "C") (pinfunction "C_C") (pintype "passive"))
    )
    (net (code "144") (name "Net-(CN22-5)") (class "Default")
      (node (ref "CN22") (pin "P$5") (pinfunction "5_P$5") (pintype "bidirectional"))
      (node (ref "D115") (pin "C") (pinfunction "C_C") (pintype "passive"))
    )
    (net (code "145") (name "Net-(CN22-6)") (class "Default")
      (node (ref "CN22") (pin "P$6") (pinfunction "6_P$6") (pintype "bidirectional"))
      (node (ref "D116") (pin "C") (pinfunction "C_C") (pintype "passive"))
    )
    (net (code "146") (name "Net-(CN22-7)") (class "Default")
      (node (ref "CN22") (pin "P$7") (pinfunction "7_P$7") (pintype "bidirectional"))
      (node (ref "D117") (pin "C") (pinfunction "C_C") (pintype "passive"))
    )
    (net (code "147") (name "Net-(CN22-8)") (class "Default")
      (node (ref "CN22") (pin "P$8") (pinfunction "8_P$8") (pintype "bidirectional"))
      (node (ref "D118") (pin "C") (pinfunction "C_C") (pintype "passive"))
    )
    (net (code "148") (name "Net-(CN22-9)") (class "Default")
      (node (ref "CN22") (pin "P$9") (pinfunction "9_P$9") (pintype "bidirectional"))
      (node (ref "D119") (pin "C") (pinfunction "C_C") (pintype "passive"))
    )
    (net (code "149") (name "Net-(CN22-10)") (class "Default")
      (node (ref "CN22") (pin "P$10") (pinfunction "10_P$10") (pintype "bidirectional"))
      (node (ref "D120") (pin "C") (pinfunction "C_C") (pintype "passive"))
    )
    (net (code "150") (name "Net-(CN22-11)") (class "Default")
      (node (ref "CN22") (pin "P$11") (pinfunction "11_P$11") (pintype "bidirectional"))
      (node (ref "D121") (pin "C") (pinfunction "C_C") (pintype "passive"))
    )
    (net (code "151") (name "Net-(CN24-1)") (class "Default")
      (node (ref "CN24") (pin "P$1") (pinfunction "1_P$1") (pintype "bidirectional"))
      (node (ref "D122") (pin "C") (pinfunction "C_C") (pintype "passive"))
    )
    (net (code "152") (name "Net-(CN24-2)") (class "Default")
      (node (ref "CN24") (pin "P$2") (pinfunction "2_P$2") (pintype "bidirectional"))
      (node (ref "D123") (pin "C") (pinfunction "C_C") (pintype "passive"))
    )
    (net (code "153") (name "Net-(CN24-3)") (class "Default")
      (node (ref "CN24") (pin "P$3") (pinfunction "3_P$3") (pintype "bidirectional"))
      (node (ref "D124") (pin "C") (pinfunction "C_C") (pintype "passive"))
    )
    (net (code "154") (name "Net-(CN24-4)") (class "Default")
      (node (ref "CN24") (pin "P$4") (pinfunction "4_P$4") (pintype "bidirectional"))
      (node (ref "D125") (pin "C") (pinfunction "C_C") (pintype "passive"))
    )
    (net (code "155") (name "Net-(CN24-5)") (class "Default")
      (node (ref "CN24") (pin "P$5") (pinfunction "5_P$5") (pintype "bidirectional"))
      (node (ref "D126") (pin "C") (pinfunction "C_C") (pintype "passive"))
    )
    (net (code "156") (name "Net-(CN24-6)") (class "Default")
      (node (ref "CN24") (pin "P$6") (pinfunction "6_P$6") (pintype "bidirectional"))
      (node (ref "D127") (pin "C") (pinfunction "C_C") (pintype "passive"))
    )
    (net (code "157") (name "Net-(CN24-7)") (class "Default")
      (node (ref "CN24") (pin "P$7") (pinfunction "7_P$7") (pintype "bidirectional"))
      (node (ref "D128") (pin "C") (pinfunction "C_C") (pintype "passive"))
    )
    (net (code "158") (name "Net-(CN24-8)") (class "Default")
      (node (ref "CN24") (pin "P$8") (pinfunction "8_P$8") (pintype "bidirectional"))
      (node (ref "D129") (pin "C") (pinfunction "C_C") (pintype "passive"))
    )
    (net (code "159") (name "Net-(CN24-9)") (class "Default")
      (node (ref "CN24") (pin "P$9") (pinfunction "9_P$9") (pintype "bidirectional"))
      (node (ref "D130") (pin "C") (pinfunction "C_C") (pintype "passive"))
    )
    (net (code "160") (name "Net-(CN24-10)") (class "Default")
      (node (ref "CN24") (pin "P$10") (pinfunction "10_P$10") (pintype "bidirectional"))
      (node (ref "D131") (pin "C") (pinfunction "C_C") (pintype "passive"))
    )
    (net (code "161") (name "Net-(CN24-11)") (class "Default")
      (node (ref "CN24") (pin "P$11") (pinfunction "11_P$11") (pintype "bidirectional"))
      (node (ref "D132") (pin "C") (pinfunction "C_C") (pintype "passive"))
    )
    (net (code "162") (name "Net-(CN26-1)") (class "Default")
      (node (ref "CN26") (pin "P$1") (pinfunction "1_P$1") (pintype "bidirectional"))
      (node (ref "D133") (pin "C") (pinfunction "C_C") (pintype "passive"))
    )
    (net (code "163") (name "Net-(CN26-2)") (class "Default")
      (node (ref "CN26") (pin "P$2") (pinfunction "2_P$2") (pintype "bidirectional"))
      (node (ref "D134") (pin "C") (pinfunction "C_C") (pintype "passive"))
    )
    (net (code "164") (name "Net-(CN26-3)") (class "Default")
      (node (ref "CN26") (pin "P$3") (pinfunction "3_P$3") (pintype "bidirectional"))
      (node (ref "D135") (pin "C") (pinfunction "C_C") (pintype "passive"))
    )
    (net (code "165") (name "Net-(CN26-4)") (class "Default")
      (node (ref "CN26") (pin "P$4") (pinfunction "4_P$4") (pintype "bidirectional"))
      (node (ref "D136") (pin "C") (pinfunction "C_C") (pintype "passive"))
    )
    (net (code "166") (name "Net-(CN26-5)") (class "Default")
      (node (ref "CN26") (pin "P$5") (pinfunction "5_P$5") (pintype "bidirectional"))
      (node (ref "D137") (pin "C") (pinfunction "C_C") (pintype "passive"))
    )
    (net (code "167") (name "Net-(CN26-6)") (class "Default")
      (node (ref "CN26") (pin "P$6") (pinfunction "6_P$6") (pintype "bidirectional"))
      (node (ref "D138") (pin "C") (pinfunction "C_C") (pintype "passive"))
    )
    (net (code "168") (name "Net-(CN26-7)") (class "Default")
      (node (ref "CN26") (pin "P$7") (pinfunction "7_P$7") (pintype "bidirectional"))
      (node (ref "D139") (pin "C") (pinfunction "C_C") (pintype "passive"))
    )
    (net (code "169") (name "Net-(CN26-8)") (class "Default")
      (node (ref "CN26") (pin "P$8") (pinfunction "8_P$8") (pintype "bidirectional"))
      (node (ref "D140") (pin "C") (pinfunction "C_C") (pintype "passive"))
    )
    (net (code "170") (name "Net-(CN26-9)") (class "Default")
      (node (ref "CN26") (pin "P$9") (pinfunction "9_P$9") (pintype "bidirectional"))
      (node (ref "D141") (pin "C") (pinfunction "C_C") (pintype "passive"))
    )
    (net (code "171") (name "Net-(CN26-10)") (class "Default")
      (node (ref "CN26") (pin "P$10") (pinfunction "10_P$10") (pintype "bidirectional"))
      (node (ref "D142") (pin "C") (pinfunction "C_C") (pintype "passive"))
    )
    (net (code "172") (name "Net-(CN26-11)") (class "Default")
      (node (ref "CN26") (pin "P$11") (pinfunction "11_P$11") (pintype "bidirectional"))
      (node (ref "D143") (pin "C") (pinfunction "C_C") (pintype "passive"))
    )
    (net (code "173") (name "Net-(CN28-1)") (class "Default")
      (node (ref "CN28") (pin "P$1") (pinfunction "1_P$1") (pintype "bidirectional"))
      (node (ref "D144") (pin "C") (pinfunction "C_C") (pintype "passive"))
    )
    (net (code "174") (name "Net-(CN28-2)") (class "Default")
      (node (ref "CN28") (pin "P$2") (pinfunction "2_P$2") (pintype "bidirectional"))
      (node (ref "D145") (pin "C") (pinfunction "C_C") (pintype "passive"))
    )
    (net (code "175") (name "Net-(CN28-3)") (class "Default")
      (node (ref "CN28") (pin "P$3") (pinfunction "3_P$3") (pintype "bidirectional"))
      (node (ref "D146") (pin "C") (pinfunction "C_C") (pintype "passive"))
    )
    (net (code "176") (name "Net-(CN28-4)") (class "Default")
      (node (ref "CN28") (pin "P$4") (pinfunction "4_P$4") (pintype "bidirectional"))
      (node (ref "D147") (pin "C") (pinfunction "C_C") (pintype "passive"))
    )
    (net (code "177") (name "Net-(CN28-5)") (class "Default")
      (node (ref "CN28") (pin "P$5") (pinfunction "5_P$5") (pintype "bidirectional"))
      (node (ref "D148") (pin "C") (pinfunction "C_C") (pintype "passive"))
    )
    (net (code "178") (name "Net-(CN28-6)") (class "Default")
      (node (ref "CN28") (pin "P$6") (pinfunction "6_P$6") (pintype "bidirectional"))
      (node (ref "D149") (pin "C") (pinfunction "C_C") (pintype "passive"))
    )
    (net (code "179") (name "Net-(CN28-7)") (class "Default")
      (node (ref "CN28") (pin "P$7") (pinfunction "7_P$7") (pintype "bidirectional"))
      (node (ref "D150") (pin "C") (pinfunction "C_C") (pintype "passive"))
    )
    (net (code "180") (name "Net-(CN28-8)") (class "Default")
      (node (ref "CN28") (pin "P$8") (pinfunction "8_P$8") (pintype "bidirectional"))
      (node (ref "D151") (pin "C") (pinfunction "C_C") (pintype "passive"))
    )
    (net (code "181") (name "Net-(CN28-9)") (class "Default")
      (node (ref "CN28") (pin "P$9") (pinfunction "9_P$9") (pintype "bidirectional"))
      (node (ref "D152") (pin "C") (pinfunction "C_C") (pintype "passive"))
    )
    (net (code "182") (name "Net-(CN28-10)") (class "Default")
      (node (ref "CN28") (pin "P$10") (pinfunction "10_P$10") (pintype "bidirectional"))
      (node (ref "D153") (pin "C") (pinfunction "C_C") (pintype "passive"))
    )
    (net (code "183") (name "Net-(CN28-11)") (class "Default")
      (node (ref "CN28") (pin "P$11") (pinfunction "11_P$11") (pintype "bidirectional"))
      (node (ref "D154") (pin "C") (pinfunction "C_C") (pintype "passive"))
    )
    (net (code "184") (name "Net-(CN30-1)") (class "Default")
      (node (ref "CN30") (pin "P$1") (pinfunction "1_P$1") (pintype "bidirectional"))
      (node (ref "D155") (pin "C") (pinfunction "C_C") (pintype "passive"))
    )
    (net (code "185") (name "Net-(CN30-2)") (class "Default")
      (node (ref "CN30") (pin "P$2") (pinfunction "2_P$2") (pintype "bidirectional"))
      (node (ref "D156") (pin "C") (pinfunction "C_C") (pintype "passive"))
    )
    (net (code "186") (name "Net-(CN30-3)") (class "Default")
      (node (ref "CN30") (pin "P$3") (pinfunction "3_P$3") (pintype "bidirectional"))
      (node (ref "D157") (pin "C") (pinfunction "C_C") (pintype "passive"))
    )
    (net (code "187") (name "Net-(CN30-4)") (class "Default")
      (node (ref "CN30") (pin "P$4") (pinfunction "4_P$4") (pintype "bidirectional"))
      (node (ref "D158") (pin "C") (pinfunction "C_C") (pintype "passive"))
    )
    (net (code "188") (name "Net-(CN30-5)") (class "Default")
      (node (ref "CN30") (pin "P$5") (pinfunction "5_P$5") (pintype "bidirectional"))
      (node (ref "D159") (pin "C") (pinfunction "C_C") (pintype "passive"))
    )
    (net (code "189") (name "Net-(CN30-6)") (class "Default")
      (node (ref "CN30") (pin "P$6") (pinfunction "6_P$6") (pintype "bidirectional"))
      (node (ref "D160") (pin "C") (pinfunction "C_C") (pintype "passive"))
    )
    (net (code "190") (name "Net-(CN30-7)") (class "Default")
      (node (ref "CN30") (pin "P$7") (pinfunction "7_P$7") (pintype "bidirectional"))
      (node (ref "D161") (pin "C") (pinfunction "C_C") (pintype "passive"))
    )
    (net (code "191") (name "Net-(CN30-8)") (class "Default")
      (node (ref "CN30") (pin "P$8") (pinfunction "8_P$8") (pintype "bidirectional"))
      (node (ref "D162") (pin "C") (pinfunction "C_C") (pintype "passive"))
    )
    (net (code "192") (name "Net-(CN30-9)") (class "Default")
      (node (ref "CN30") (pin "P$9") (pinfunction "9_P$9") (pintype "bidirectional"))
      (node (ref "D163") (pin "C") (pinfunction "C_C") (pintype "passive"))
    )
    (net (code "193") (name "Net-(CN30-10)") (class "Default")
      (node (ref "CN30") (pin "P$10") (pinfunction "10_P$10") (pintype "bidirectional"))
      (node (ref "D164") (pin "C") (pinfunction "C_C") (pintype "passive"))
    )
    (net (code "194") (name "Net-(CN30-11)") (class "Default")
      (node (ref "CN30") (pin "P$11") (pinfunction "11_P$11") (pintype "bidirectional"))
      (node (ref "D165") (pin "C") (pinfunction "C_C") (pintype "passive"))
    )
    (net (code "195") (name "Net-(CN32-1)") (class "Default")
      (node (ref "CN32") (pin "P$1") (pinfunction "1_P$1") (pintype "bidirectional"))
      (node (ref "D166") (pin "C") (pinfunction "C_C") (pintype "passive"))
    )
    (net (code "196") (name "Net-(CN32-2)") (class "Default")
      (node (ref "CN32") (pin "P$2") (pinfunction "2_P$2") (pintype "bidirectional"))
      (node (ref "D167") (pin "C") (pinfunction "C_C") (pintype "passive"))
    )
    (net (code "197") (name "Net-(CN32-3)") (class "Default")
      (node (ref "CN32") (pin "P$3") (pinfunction "3_P$3") (pintype "bidirectional"))
      (node (ref "D168") (pin "C") (pinfunction "C_C") (pintype "passive"))
    )
    (net (code "198") (name "Net-(CN32-4)") (class "Default")
      (node (ref "CN32") (pin "P$4") (pinfunction "4_P$4") (pintype "bidirectional"))
      (node (ref "D169") (pin "C") (pinfunction "C_C") (pintype "passive"))
    )
    (net (code "199") (name "Net-(CN32-5)") (class "Default")
      (node (ref "CN32") (pin "P$5") (pinfunction "5_P$5") (pintype "bidirectional"))
      (node (ref "D170") (pin "C") (pinfunction "C_C") (pintype "passive"))
    )
    (net (code "200") (name "Net-(CN32-6)") (class "Default")
      (node (ref "CN32") (pin "P$6") (pinfunction "6_P$6") (pintype "bidirectional"))
      (node (ref "D171") (pin "C") (pinfunction "C_C") (pintype "passive"))
    )
    (net (code "201") (name "Net-(CN32-7)") (class "Default")
      (node (ref "CN32") (pin "P$7") (pinfunction "7_P$7") (pintype "bidirectional"))
      (node (ref "D172") (pin "C") (pinfunction "C_C") (pintype "passive"))
    )
    (net (code "202") (name "Net-(CN32-8)") (class "Default")
      (node (ref "CN32") (pin "P$8") (pinfunction "8_P$8") (pintype "bidirectional"))
      (node (ref "D173") (pin "C") (pinfunction "C_C") (pintype "passive"))
    )
    (net (code "203") (name "Net-(CN32-9)") (class "Default")
      (node (ref "CN32") (pin "P$9") (pinfunction "9_P$9") (pintype "bidirectional"))
      (node (ref "D174") (pin "C") (pinfunction "C_C") (pintype "passive"))
    )
    (net (code "204") (name "Net-(CN32-10)") (class "Default")
      (node (ref "CN32") (pin "P$10") (pinfunction "10_P$10") (pintype "bidirectional"))
      (node (ref "D175") (pin "C") (pinfunction "C_C") (pintype "passive"))
    )
    (net (code "205") (name "Net-(CN32-11)") (class "Default")
      (node (ref "CN32") (pin "P$11") (pinfunction "11_P$11") (pintype "bidirectional"))
      (node (ref "D176") (pin "C") (pinfunction "C_C") (pintype "passive"))
    )
    (net (code "206") (name "Net-(CN34-3)") (class "Default")
      (node (ref "CN34") (pin "P$3") (pinfunction "3_P$3") (pintype "bidirectional"))
      (node (ref "VR1") (pin "IN@1") (pinfunction "VIN_IN@1") (pintype "power_in"))
      (node (ref "VR1") (pin "IN@2") (pinfunction "VIN_IN@2") (pintype "power_in"))
    )
    (net (code "207") (name "RE0") (class "Default")
      (node (ref "D197") (pin "A") (pinfunction "A_A") (pintype "passive"))
      (node (ref "D208") (pin "A") (pinfunction "A_A") (pintype "passive"))
      (node (ref "R18") (pin "1") (pinfunction "1_1") (pintype "passive"))
    )
    (net (code "208") (name "RE1") (class "Default")
      (node (ref "D196") (pin "A") (pinfunction "A_A") (pintype "passive"))
      (node (ref "D207") (pin "A") (pinfunction "A_A") (pintype "passive"))
      (node (ref "R17") (pin "1") (pinfunction "1_1") (pintype "passive"))
    )
    (net (code "209") (name "RE2") (class "Default")
      (node (ref "D195") (pin "A") (pinfunction "A_A") (pintype "passive"))
      (node (ref "D206") (pin "A") (pinfunction "A_A") (pintype "passive"))
      (node (ref "R16") (pin "1") (pinfunction "1_1") (pintype "passive"))
    )
    (net (code "210") (name "RE3") (class "Default")
      (node (ref "D194") (pin "A") (pinfunction "A_A") (pintype "passive"))
      (node (ref "D205") (pin "A") (pinfunction "A_A") (pintype "passive"))
      (node (ref "R15") (pin "1") (pinfunction "1_1") (pintype "passive"))
    )
    (net (code "211") (name "RE4") (class "Default")
      (node (ref "D193") (pin "A") (pinfunction "A_A") (pintype "passive"))
      (node (ref "D204") (pin "A") (pinfunction "A_A") (pintype "passive"))
      (node (ref "R14") (pin "1") (pinfunction "1_1") (pintype "passive"))
    )
    (net (code "212") (name "RE5") (class "Default")
      (node (ref "D192") (pin "A") (pinfunction "A_A") (pintype "passive"))
      (node (ref "D203") (pin "A") (pinfunction "A_A") (pintype "passive"))
      (node (ref "R13") (pin "1") (pinfunction "1_1") (pintype "passive"))
    )
    (net (code "213") (name "RE6") (class "Default")
      (node (ref "D191") (pin "A") (pinfunction "A_A") (pintype "passive"))
      (node (ref "D202") (pin "A") (pinfunction "A_A") (pintype "passive"))
      (node (ref "R12") (pin "1") (pinfunction "1_1") (pintype "passive"))
    )
    (net (code "214") (name "RE7") (class "Default")
      (node (ref "D190") (pin "A") (pinfunction "A_A") (pintype "passive"))
      (node (ref "D201") (pin "A") (pinfunction "A_A") (pintype "passive"))
      (node (ref "R11") (pin "1") (pinfunction "1_1") (pintype "passive"))
    )
    (net (code "215") (name "RE8") (class "Default")
      (node (ref "D189") (pin "A") (pinfunction "A_A") (pintype "passive"))
      (node (ref "D200") (pin "A") (pinfunction "A_A") (pintype "passive"))
      (node (ref "R10") (pin "1") (pinfunction "1_1") (pintype "passive"))
    )
    (net (code "216") (name "RE9") (class "Default")
      (node (ref "D188") (pin "A") (pinfunction "A_A") (pintype "passive"))
      (node (ref "D199") (pin "A") (pinfunction "A_A") (pintype "passive"))
      (node (ref "R9") (pin "1") (pinfunction "1_1") (pintype "passive"))
    )
    (net (code "217") (name "RE10") (class "Default")
      (node (ref "D187") (pin "A") (pinfunction "A_A") (pintype "passive"))
      (node (ref "D198") (pin "A") (pinfunction "A_A") (pintype "passive"))
      (node (ref "R8") (pin "1") (pinfunction "1_1") (pintype "passive"))
    )
    (net (code "218") (name "RE11") (class "Default")
      (node (ref "D181") (pin "A") (pinfunction "A_A") (pintype "passive"))
      (node (ref "D186") (pin "A") (pinfunction "A_A") (pintype "passive"))
      (node (ref "R7") (pin "1") (pinfunction "1_1") (pintype "passive"))
    )
    (net (code "219") (name "RE12") (class "Default")
      (node (ref "D180") (pin "A") (pinfunction "A_A") (pintype "passive"))
      (node (ref "D185") (pin "A") (pinfunction "A_A") (pintype "passive"))
      (node (ref "R6") (pin "1") (pinfunction "1_1") (pintype "passive"))
    )
    (net (code "220") (name "RE13") (class "Default")
      (node (ref "D179") (pin "A") (pinfunction "A_A") (pintype "passive"))
      (node (ref "D184") (pin "A") (pinfunction "A_A") (pintype "passive"))
      (node (ref "R5") (pin "1") (pinfunction "1_1") (pintype "passive"))
    )
    (net (code "221") (name "RE14") (class "Default")
      (node (ref "D178") (pin "A") (pinfunction "A_A") (pintype "passive"))
      (node (ref "D183") (pin "A") (pinfunction "A_A") (pintype "passive"))
      (node (ref "R4") (pin "1") (pinfunction "1_1") (pintype "passive"))
    )
    (net (code "222") (name "RE15") (class "Default")
      (node (ref "D177") (pin "A") (pinfunction "A_A") (pintype "passive"))
      (node (ref "D182") (pin "A") (pinfunction "A_A") (pintype "passive"))
      (node (ref "R2") (pin "1") (pinfunction "1_1") (pintype "passive"))
    )
    (net (code "223") (name "ROW0") (class "Default")
      (node (ref "CN2") (pin "P$1") (pinfunction "1_P$1") (pintype "bidirectional"))
      (node (ref "CN2") (pin "P$10") (pinfunction "10_P$10") (pintype "bidirectional"))
      (node (ref "CN2") (pin "P$11") (pinfunction "11_P$11") (pintype "bidirectional"))
      (node (ref "CN2") (pin "P$2") (pinfunction "2_P$2") (pintype "bidirectional"))
      (node (ref "CN2") (pin "P$3") (pinfunction "3_P$3") (pintype "bidirectional"))
      (node (ref "CN2") (pin "P$4") (pinfunction "4_P$4") (pintype "bidirectional"))
      (node (ref "CN2") (pin "P$5") (pinfunction "5_P$5") (pintype "bidirectional"))
      (node (ref "CN2") (pin "P$6") (pinfunction "6_P$6") (pintype "bidirectional"))
      (node (ref "CN2") (pin "P$7") (pinfunction "7_P$7") (pintype "bidirectional"))
      (node (ref "CN2") (pin "P$8") (pinfunction "8_P$8") (pintype "bidirectional"))
      (node (ref "CN2") (pin "P$9") (pinfunction "9_P$9") (pintype "bidirectional"))
      (node (ref "Q1") (pin "C") (pinfunction "C_C") (pintype "passive"))
      (node (ref "R1") (pin "1") (pinfunction "1_1") (pintype "passive"))
    )
    (net (code "224") (name "ROW1") (class "Default")
      (node (ref "CN4") (pin "P$1") (pinfunction "1_P$1") (pintype "bidirectional"))
      (node (ref "CN4") (pin "P$10") (pinfunction "10_P$10") (pintype "bidirectional"))
      (node (ref "CN4") (pin "P$11") (pinfunction "11_P$11") (pintype "bidirectional"))
      (node (ref "CN4") (pin "P$2") (pinfunction "2_P$2") (pintype "bidirectional"))
      (node (ref "CN4") (pin "P$3") (pinfunction "3_P$3") (pintype "bidirectional"))
      (node (ref "CN4") (pin "P$4") (pinfunction "4_P$4") (pintype "bidirectional"))
      (node (ref "CN4") (pin "P$5") (pinfunction "5_P$5") (pintype "bidirectional"))
      (node (ref "CN4") (pin "P$6") (pinfunction "6_P$6") (pintype "bidirectional"))
      (node (ref "CN4") (pin "P$7") (pinfunction "7_P$7") (pintype "bidirectional"))
      (node (ref "CN4") (pin "P$8") (pinfunction "8_P$8") (pintype "bidirectional"))
      (node (ref "CN4") (pin "P$9") (pinfunction "9_P$9") (pintype "bidirectional"))
      (node (ref "Q2") (pin "C") (pinfunction "C_C") (pintype "passive"))
      (node (ref "R3") (pin "1") (pinfunction "1_1") (pintype "passive"))
    )
    (net (code "225") (name "ROW2") (class "Default")
      (node (ref "CN6") (pin "P$1") (pinfunction "1_P$1") (pintype "bidirectional"))
      (node (ref "CN6") (pin "P$10") (pinfunction "10_P$10") (pintype "bidirectional"))
      (node (ref "CN6") (pin "P$11") (pinfunction "11_P$11") (pintype "bidirectional"))
      (node (ref "CN6") (pin "P$2") (pinfunction "2_P$2") (pintype "bidirectional"))
      (node (ref "CN6") (pin "P$3") (pinfunction "3_P$3") (pintype "bidirectional"))
      (node (ref "CN6") (pin "P$4") (pinfunction "4_P$4") (pintype "bidirectional"))
      (node (ref "CN6") (pin "P$5") (pinfunction "5_P$5") (pintype "bidirectional"))
      (node (ref "CN6") (pin "P$6") (pinfunction "6_P$6") (pintype "bidirectional"))
      (node (ref "CN6") (pin "P$7") (pinfunction "7_P$7") (pintype "bidirectional"))
      (node (ref "CN6") (pin "P$8") (pinfunction "8_P$8") (pintype "bidirectional"))
      (node (ref "CN6") (pin "P$9") (pinfunction "9_P$9") (pintype "bidirectional"))
      (node (ref "Q3") (pin "C") (pinfunction "C_C") (pintype "passive"))
      (node (ref "R19") (pin "1") (pinfunction "1_1") (pintype "passive"))
    )
    (net (code "226") (name "ROW3") (class "Default")
      (node (ref "CN9") (pin "P$1") (pinfunction "1_P$1") (pintype "bidirectional"))
      (node (ref "CN9") (pin "P$10") (pinfunction "10_P$10") (pintype "bidirectional"))
      (node (ref "CN9") (pin "P$11") (pinfunction "11_P$11") (pintype "bidirectional"))
      (node (ref "CN9") (pin "P$2") (pinfunction "2_P$2") (pintype "bidirectional"))
      (node (ref "CN9") (pin "P$3") (pinfunction "3_P$3") (pintype "bidirectional"))
      (node (ref "CN9") (pin "P$4") (pinfunction "4_P$4") (pintype "bidirectional"))
      (node (ref "CN9") (pin "P$5") (pinfunction "5_P$5") (pintype "bidirectional"))
      (node (ref "CN9") (pin "P$6") (pinfunction "6_P$6") (pintype "bidirectional"))
      (node (ref "CN9") (pin "P$7") (pinfunction "7_P$7") (pintype "bidirectional"))
      (node (ref "CN9") (pin "P$8") (pinfunction "8_P$8") (pintype "bidirectional"))
      (node (ref "CN9") (pin "P$9") (pinfunction "9_P$9") (pintype "bidirectional"))
      (node (ref "Q4") (pin "C") (pinfunction "C_C") (pintype "passive"))
      (node (ref "R20") (pin "1") (pinfunction "1_1") (pintype "passive"))
    )
    (net (code "227") (name "ROW4") (class "Default")
      (node (ref "CN10") (pin "P$1") (pinfunction "1_P$1") (pintype "bidirectional"))
      (node (ref "CN10") (pin "P$10") (pinfunction "10_P$10") (pintype "bidirectional"))
      (node (ref "CN10") (pin "P$11") (pinfunction "11_P$11") (pintype "bidirectional"))
      (node (ref "CN10") (pin "P$2") (pinfunction "2_P$2") (pintype "bidirectional"))
      (node (ref "CN10") (pin "P$3") (pinfunction "3_P$3") (pintype "bidirectional"))
      (node (ref "CN10") (pin "P$4") (pinfunction "4_P$4") (pintype "bidirectional"))
      (node (ref "CN10") (pin "P$5") (pinfunction "5_P$5") (pintype "bidirectional"))
      (node (ref "CN10") (pin "P$6") (pinfunction "6_P$6") (pintype "bidirectional"))
      (node (ref "CN10") (pin "P$7") (pinfunction "7_P$7") (pintype "bidirectional"))
      (node (ref "CN10") (pin "P$8") (pinfunction "8_P$8") (pintype "bidirectional"))
      (node (ref "CN10") (pin "P$9") (pinfunction "9_P$9") (pintype "bidirectional"))
      (node (ref "Q5") (pin "C") (pinfunction "C_C") (pintype "passive"))
      (node (ref "R21") (pin "1") (pinfunction "1_1") (pintype "passive"))
    )
    (net (code "228") (name "ROW5") (class "Default")
      (node (ref "CN13") (pin "P$1") (pinfunction "1_P$1") (pintype "bidirectional"))
      (node (ref "CN13") (pin "P$10") (pinfunction "10_P$10") (pintype "bidirectional"))
      (node (ref "CN13") (pin "P$11") (pinfunction "11_P$11") (pintype "bidirectional"))
      (node (ref "CN13") (pin "P$2") (pinfunction "2_P$2") (pintype "bidirectional"))
      (node (ref "CN13") (pin "P$3") (pinfunction "3_P$3") (pintype "bidirectional"))
      (node (ref "CN13") (pin "P$4") (pinfunction "4_P$4") (pintype "bidirectional"))
      (node (ref "CN13") (pin "P$5") (pinfunction "5_P$5") (pintype "bidirectional"))
      (node (ref "CN13") (pin "P$6") (pinfunction "6_P$6") (pintype "bidirectional"))
      (node (ref "CN13") (pin "P$7") (pinfunction "7_P$7") (pintype "bidirectional"))
      (node (ref "CN13") (pin "P$8") (pinfunction "8_P$8") (pintype "bidirectional"))
      (node (ref "CN13") (pin "P$9") (pinfunction "9_P$9") (pintype "bidirectional"))
      (node (ref "Q6") (pin "C") (pinfunction "C_C") (pintype "passive"))
      (node (ref "R22") (pin "1") (pinfunction "1_1") (pintype "passive"))
    )
    (net (code "229") (name "ROW6") (class "Default")
      (node (ref "CN15") (pin "P$1") (pinfunction "1_P$1") (pintype "bidirectional"))
      (node (ref "CN15") (pin "P$10") (pinfunction "10_P$10") (pintype "bidirectional"))
      (node (ref "CN15") (pin "P$11") (pinfunction "11_P$11") (pintype "bidirectional"))
      (node (ref "CN15") (pin "P$2") (pinfunction "2_P$2") (pintype "bidirectional"))
      (node (ref "CN15") (pin "P$3") (pinfunction "3_P$3") (pintype "bidirectional"))
      (node (ref "CN15") (pin "P$4") (pinfunction "4_P$4") (pintype "bidirectional"))
      (node (ref "CN15") (pin "P$5") (pinfunction "5_P$5") (pintype "bidirectional"))
      (node (ref "CN15") (pin "P$6") (pinfunction "6_P$6") (pintype "bidirectional"))
      (node (ref "CN15") (pin "P$7") (pinfunction "7_P$7") (pintype "bidirectional"))
      (node (ref "CN15") (pin "P$8") (pinfunction "8_P$8") (pintype "bidirectional"))
      (node (ref "CN15") (pin "P$9") (pinfunction "9_P$9") (pintype "bidirectional"))
      (node (ref "Q7") (pin "C") (pinfunction "C_C") (pintype "passive"))
      (node (ref "R23") (pin "1") (pinfunction "1_1") (pintype "passive"))
    )
    (net (code "230") (name "ROW7") (class "Default")
      (node (ref "CN17") (pin "P$1") (pinfunction "1_P$1") (pintype "bidirectional"))
      (node (ref "CN17") (pin "P$10") (pinfunction "10_P$10") (pintype "bidirectional"))
      (node (ref "CN17") (pin "P$11") (pinfunction "11_P$11") (pintype "bidirectional"))
      (node (ref "CN17") (pin "P$2") (pinfunction "2_P$2") (pintype "bidirectional"))
      (node (ref "CN17") (pin "P$3") (pinfunction "3_P$3") (pintype "bidirectional"))
      (node (ref "CN17") (pin "P$4") (pinfunction "4_P$4") (pintype "bidirectional"))
      (node (ref "CN17") (pin "P$5") (pinfunction "5_P$5") (pintype "bidirectional"))
      (node (ref "CN17") (pin "P$6") (pinfunction "6_P$6") (pintype "bidirectional"))
      (node (ref "CN17") (pin "P$7") (pinfunction "7_P$7") (pintype "bidirectional"))
      (node (ref "CN17") (pin "P$8") (pinfunction "8_P$8") (pintype "bidirectional"))
      (node (ref "CN17") (pin "P$9") (pinfunction "9_P$9") (pintype "bidirectional"))
      (node (ref "Q8") (pin "C") (pinfunction "C_C") (pintype "passive"))
      (node (ref "R24") (pin "1") (pinfunction "1_1") (pintype "passive"))
    )
    (net (code "231") (name "ROW8") (class "Default")
      (node (ref "CN18") (pin "P$1") (pinfunction "1_P$1") (pintype "bidirectional"))
      (node (ref "CN18") (pin "P$10") (pinfunction "10_P$10") (pintype "bidirectional"))
      (node (ref "CN18") (pin "P$11") (pinfunction "11_P$11") (pintype "bidirectional"))
      (node (ref "CN18") (pin "P$2") (pinfunction "2_P$2") (pintype "bidirectional"))
      (node (ref "CN18") (pin "P$3") (pinfunction "3_P$3") (pintype "bidirectional"))
      (node (ref "CN18") (pin "P$4") (pinfunction "4_P$4") (pintype "bidirectional"))
      (node (ref "CN18") (pin "P$5") (pinfunction "5_P$5") (pintype "bidirectional"))
      (node (ref "CN18") (pin "P$6") (pinfunction "6_P$6") (pintype "bidirectional"))
      (node (ref "CN18") (pin "P$7") (pinfunction "7_P$7") (pintype "bidirectional"))
      (node (ref "CN18") (pin "P$8") (pinfunction "8_P$8") (pintype "bidirectional"))
      (node (ref "CN18") (pin "P$9") (pinfunction "9_P$9") (pintype "bidirectional"))
      (node (ref "Q9") (pin "C") (pinfunction "C_C") (pintype "passive"))
      (node (ref "R25") (pin "1") (pinfunction "1_1") (pintype "passive"))
    )
    (net (code "232") (name "ROW9") (class "Default")
      (node (ref "CN21") (pin "P$1") (pinfunction "1_P$1") (pintype "bidirectional"))
      (node (ref "CN21") (pin "P$10") (pinfunction "10_P$10") (pintype "bidirectional"))
      (node (ref "CN21") (pin "P$11") (pinfunction "11_P$11") (pintype "bidirectional"))
      (node (ref "CN21") (pin "P$2") (pinfunction "2_P$2") (pintype "bidirectional"))
      (node (ref "CN21") (pin "P$3") (pinfunction "3_P$3") (pintype "bidirectional"))
      (node (ref "CN21") (pin "P$4") (pinfunction "4_P$4") (pintype "bidirectional"))
      (node (ref "CN21") (pin "P$5") (pinfunction "5_P$5") (pintype "bidirectional"))
      (node (ref "CN21") (pin "P$6") (pinfunction "6_P$6") (pintype "bidirectional"))
      (node (ref "CN21") (pin "P$7") (pinfunction "7_P$7") (pintype "bidirectional"))
      (node (ref "CN21") (pin "P$8") (pinfunction "8_P$8") (pintype "bidirectional"))
      (node (ref "CN21") (pin "P$9") (pinfunction "9_P$9") (pintype "bidirectional"))
      (node (ref "Q10") (pin "C") (pinfunction "C_C") (pintype "passive"))
      (node (ref "R26") (pin "1") (pinfunction "1_1") (pintype "passive"))
    )
    (net (code "233") (name "ROW10") (class "Default")
      (node (ref "CN23") (pin "P$1") (pinfunction "1_P$1") (pintype "bidirectional"))
      (node (ref "CN23") (pin "P$10") (pinfunction "10_P$10") (pintype "bidirectional"))
      (node (ref "CN23") (pin "P$11") (pinfunction "11_P$11") (pintype "bidirectional"))
      (node (ref "CN23") (pin "P$2") (pinfunction "2_P$2") (pintype "bidirectional"))
      (node (ref "CN23") (pin "P$3") (pinfunction "3_P$3") (pintype "bidirectional"))
      (node (ref "CN23") (pin "P$4") (pinfunction "4_P$4") (pintype "bidirectional"))
      (node (ref "CN23") (pin "P$5") (pinfunction "5_P$5") (pintype "bidirectional"))
      (node (ref "CN23") (pin "P$6") (pinfunction "6_P$6") (pintype "bidirectional"))
      (node (ref "CN23") (pin "P$7") (pinfunction "7_P$7") (pintype "bidirectional"))
      (node (ref "CN23") (pin "P$8") (pinfunction "8_P$8") (pintype "bidirectional"))
      (node (ref "CN23") (pin "P$9") (pinfunction "9_P$9") (pintype "bidirectional"))
      (node (ref "Q11") (pin "C") (pinfunction "C_C") (pintype "passive"))
      (node (ref "R27") (pin "1") (pinfunction "1_1") (pintype "passive"))
    )
    (net (code "234") (name "ROW11") (class "Default")
      (node (ref "CN25") (pin "P$1") (pinfunction "1_P$1") (pintype "bidirectional"))
      (node (ref "CN25") (pin "P$10") (pinfunction "10_P$10") (pintype "bidirectional"))
      (node (ref "CN25") (pin "P$11") (pinfunction "11_P$11") (pintype "bidirectional"))
      (node (ref "CN25") (pin "P$2") (pinfunction "2_P$2") (pintype "bidirectional"))
      (node (ref "CN25") (pin "P$3") (pinfunction "3_P$3") (pintype "bidirectional"))
      (node (ref "CN25") (pin "P$4") (pinfunction "4_P$4") (pintype "bidirectional"))
      (node (ref "CN25") (pin "P$5") (pinfunction "5_P$5") (pintype "bidirectional"))
      (node (ref "CN25") (pin "P$6") (pinfunction "6_P$6") (pintype "bidirectional"))
      (node (ref "CN25") (pin "P$7") (pinfunction "7_P$7") (pintype "bidirectional"))
      (node (ref "CN25") (pin "P$8") (pinfunction "8_P$8") (pintype "bidirectional"))
      (node (ref "CN25") (pin "P$9") (pinfunction "9_P$9") (pintype "bidirectional"))
      (node (ref "Q12") (pin "C") (pinfunction "C_C") (pintype "passive"))
      (node (ref "R28") (pin "1") (pinfunction "1_1") (pintype "passive"))
    )
    (net (code "235") (name "ROW12") (class "Default")
      (node (ref "CN27") (pin "P$1") (pinfunction "1_P$1") (pintype "bidirectional"))
      (node (ref "CN27") (pin "P$10") (pinfunction "10_P$10") (pintype "bidirectional"))
      (node (ref "CN27") (pin "P$11") (pinfunction "11_P$11") (pintype "bidirectional"))
      (node (ref "CN27") (pin "P$2") (pinfunction "2_P$2") (pintype "bidirectional"))
      (node (ref "CN27") (pin "P$3") (pinfunction "3_P$3") (pintype "bidirectional"))
      (node (ref "CN27") (pin "P$4") (pinfunction "4_P$4") (pintype "bidirectional"))
      (node (ref "CN27") (pin "P$5") (pinfunction "5_P$5") (pintype "bidirectional"))
      (node (ref "CN27") (pin "P$6") (pinfunction "6_P$6") (pintype "bidirectional"))
      (node (ref "CN27") (pin "P$7") (pinfunction "7_P$7") (pintype "bidirectional"))
      (node (ref "CN27") (pin "P$8") (pinfunction "8_P$8") (pintype "bidirectional"))
      (node (ref "CN27") (pin "P$9") (pinfunction "9_P$9") (pintype "bidirectional"))
      (node (ref "Q13") (pin "C") (pinfunction "C_C") (pintype "passive"))
      (node (ref "R29") (pin "1") (pinfunction "1_1") (pintype "passive"))
    )
    (net (code "236") (name "ROW13") (class "Default")
      (node (ref "CN29") (pin "P$1") (pinfunction "1_P$1") (pintype "bidirectional"))
      (node (ref "CN29") (pin "P$10") (pinfunction "10_P$10") (pintype "bidirectional"))
      (node (ref "CN29") (pin "P$11") (pinfunction "11_P$11") (pintype "bidirectional"))
      (node (ref "CN29") (pin "P$2") (pinfunction "2_P$2") (pintype "bidirectional"))
      (node (ref "CN29") (pin "P$3") (pinfunction "3_P$3") (pintype "bidirectional"))
      (node (ref "CN29") (pin "P$4") (pinfunction "4_P$4") (pintype "bidirectional"))
      (node (ref "CN29") (pin "P$5") (pinfunction "5_P$5") (pintype "bidirectional"))
      (node (ref "CN29") (pin "P$6") (pinfunction "6_P$6") (pintype "bidirectional"))
      (node (ref "CN29") (pin "P$7") (pinfunction "7_P$7") (pintype "bidirectional"))
      (node (ref "CN29") (pin "P$8") (pinfunction "8_P$8") (pintype "bidirectional"))
      (node (ref "CN29") (pin "P$9") (pinfunction "9_P$9") (pintype "bidirectional"))
      (node (ref "Q14") (pin "C") (pinfunction "C_C") (pintype "passive"))
      (node (ref "R30") (pin "1") (pinfunction "1_1") (pintype "passive"))
    )
    (net (code "237") (name "ROW14") (class "Default")
      (node (ref "CN31") (pin "P$1") (pinfunction "1_P$1") (pintype "bidirectional"))
      (node (ref "CN31") (pin "P$10") (pinfunction "10_P$10") (pintype "bidirectional"))
      (node (ref "CN31") (pin "P$11") (pinfunction "11_P$11") (pintype "bidirectional"))
      (node (ref "CN31") (pin "P$2") (pinfunction "2_P$2") (pintype "bidirectional"))
      (node (ref "CN31") (pin "P$3") (pinfunction "3_P$3") (pintype "bidirectional"))
      (node (ref "CN31") (pin "P$4") (pinfunction "4_P$4") (pintype "bidirectional"))
      (node (ref "CN31") (pin "P$5") (pinfunction "5_P$5") (pintype "bidirectional"))
      (node (ref "CN31") (pin "P$6") (pinfunction "6_P$6") (pintype "bidirectional"))
      (node (ref "CN31") (pin "P$7") (pinfunction "7_P$7") (pintype "bidirectional"))
      (node (ref "CN31") (pin "P$8") (pinfunction "8_P$8") (pintype "bidirectional"))
      (node (ref "CN31") (pin "P$9") (pinfunction "9_P$9") (pintype "bidirectional"))
      (node (ref "Q15") (pin "C") (pinfunction "C_C") (pintype "passive"))
      (node (ref "R31") (pin "1") (pinfunction "1_1") (pintype "passive"))
    )
    (net (code "238") (name "ROW15") (class "Default")
      (node (ref "CN33") (pin "P$1") (pinfunction "1_P$1") (pintype "bidirectional"))
      (node (ref "CN33") (pin "P$10") (pinfunction "10_P$10") (pintype "bidirectional"))
      (node (ref "CN33") (pin "P$11") (pinfunction "11_P$11") (pintype "bidirectional"))
      (node (ref "CN33") (pin "P$2") (pinfunction "2_P$2") (pintype "bidirectional"))
      (node (ref "CN33") (pin "P$3") (pinfunction "3_P$3") (pintype "bidirectional"))
      (node (ref "CN33") (pin "P$4") (pinfunction "4_P$4") (pintype "bidirectional"))
      (node (ref "CN33") (pin "P$5") (pinfunction "5_P$5") (pintype "bidirectional"))
      (node (ref "CN33") (pin "P$6") (pinfunction "6_P$6") (pintype "bidirectional"))
      (node (ref "CN33") (pin "P$7") (pinfunction "7_P$7") (pintype "bidirectional"))
      (node (ref "CN33") (pin "P$8") (pinfunction "8_P$8") (pintype "bidirectional"))
      (node (ref "CN33") (pin "P$9") (pinfunction "9_P$9") (pintype "bidirectional"))
      (node (ref "Q16") (pin "C") (pinfunction "C_C") (pintype "passive"))
      (node (ref "R32") (pin "1") (pinfunction "1_1") (pintype "passive"))
    )
    (net (code "239") (name "V+") (class "Default")
      (node (ref "R1") (pin "2") (pinfunction "2_2") (pintype "passive"))
      (node (ref "R10") (pin "2") (pinfunction "2_2") (pintype "passive"))
      (node (ref "R11") (pin "2") (pinfunction "2_2") (pintype "passive"))
      (node (ref "R12") (pin "2") (pinfunction "2_2") (pintype "passive"))
      (node (ref "R13") (pin "2") (pinfunction "2_2") (pintype "passive"))
      (node (ref "R14") (pin "2") (pinfunction "2_2") (pintype "passive"))
      (node (ref "R15") (pin "2") (pinfunction "2_2") (pintype "passive"))
      (node (ref "R16") (pin "2") (pinfunction "2_2") (pintype "passive"))
      (node (ref "R17") (pin "2") (pinfunction "2_2") (pintype "passive"))
      (node (ref "R18") (pin "2") (pinfunction "2_2") (pintype "passive"))
      (node (ref "R19") (pin "2") (pinfunction "2_2") (pintype "passive"))
      (node (ref "R2") (pin "2") (pinfunction "2_2") (pintype "passive"))
      (node (ref "R20") (pin "2") (pinfunction "2_2") (pintype "passive"))
      (node (ref "R21") (pin "2") (pinfunction "2_2") (pintype "passive"))
      (node (ref "R22") (pin "2") (pinfunction "2_2") (pintype "passive"))
      (node (ref "R23") (pin "2") (pinfunction "2_2") (pintype "passive"))
      (node (ref "R24") (pin "2") (pinfunction "2_2") (pintype "passive"))
      (node (ref "R25") (pin "2") (pinfunction "2_2") (pintype "passive"))
      (node (ref "R26") (pin "2") (pinfunction "2_2") (pintype "passive"))
      (node (ref "R27") (pin "2") (pinfunction "2_2") (pintype "passive"))
      (node (ref "R28") (pin "2") (pinfunction "2_2") (pintype "passive"))
      (node (ref "R29") (pin "2") (pinfunction "2_2") (pintype "passive"))
      (node (ref "R3") (pin "2") (pinfunction "2_2") (pintype "passive"))
      (node (ref "R30") (pin "2") (pinfunction "2_2") (pintype "passive"))
      (node (ref "R31") (pin "2") (pinfunction "2_2") (pintype "passive"))
      (node (ref "R32") (pin "2") (pinfunction "2_2") (pintype "passive"))
      (node (ref "R4") (pin "2") (pinfunction "2_2") (pintype "passive"))
      (node (ref "R5") (pin "2") (pinfunction "2_2") (pintype "passive"))
      (node (ref "R6") (pin "2") (pinfunction "2_2") (pintype "passive"))
      (node (ref "R7") (pin "2") (pinfunction "2_2") (pintype "passive"))
      (node (ref "R8") (pin "2") (pinfunction "2_2") (pintype "passive"))
      (node (ref "R9") (pin "2") (pinfunction "2_2") (pintype "passive"))
      (node (ref "VR1") (pin "OUT@1") (pinfunction "VOUT_OUT@1") (pintype "power_in"))
      (node (ref "VR1") (pin "OUT@2") (pinfunction "VOUT_OUT@2") (pintype "power_in"))
    )
    (net (code "240") (name "unconnected-(Q1-PadB)") (class "Default")
      (node (ref "Q1") (pin "B") (pinfunction "B_B") (pintype "passive"))
    )
    (net (code "241") (name "unconnected-(Q2-PadB)") (class "Default")
      (node (ref "Q2") (pin "B") (pinfunction "B_B") (pintype "passive"))
    )
    (net (code "242") (name "unconnected-(Q3-PadB)") (class "Default")
      (node (ref "Q3") (pin "B") (pinfunction "B_B") (pintype "passive"))
    )
    (net (code "243") (name "unconnected-(Q4-PadB)") (class "Default")
      (node (ref "Q4") (pin "B") (pinfunction "B_B") (pintype "passive"))
    )
    (net (code "244") (name "unconnected-(Q5-PadB)") (class "Default")
      (node (ref "Q5") (pin "B") (pinfunction "B_B") (pintype "passive"))
    )
    (net (code "245") (name "unconnected-(Q6-PadB)") (class "Default")
      (node (ref "Q6") (pin "B") (pinfunction "B_B") (pintype "passive"))
    )
    (net (code "246") (name "unconnected-(Q7-PadB)") (class "Default")
      (node (ref "Q7") (pin "B") (pinfunction "B_B") (pintype "passive"))
    )
    (net (code "247") (name "unconnected-(Q8-PadB)") (class "Default")
      (node (ref "Q8") (pin "B") (pinfunction "B_B") (pintype "passive"))
    )
    (net (code "248") (name "unconnected-(Q9-PadB)") (class "Default")
      (node (ref "Q9") (pin "B") (pinfunction "B_B") (pintype "passive"))
    )
    (net (code "249") (name "unconnected-(Q10-PadB)") (class "Default")
      (node (ref "Q10") (pin "B") (pinfunction "B_B") (pintype "passive"))
    )
    (net (code "250") (name "unconnected-(Q11-PadB)") (class "Default")
      (node (ref "Q11") (pin "B") (pinfunction "B_B") (pintype "passive"))
    )
    (net (code "251") (name "unconnected-(Q12-PadB)") (class "Default")
      (node (ref "Q12") (pin "B") (pinfunction "B_B") (pintype "passive"))
    )
    (net (code "252") (name "unconnected-(Q13-PadB)") (class "Default")
      (node (ref "Q13") (pin "B") (pinfunction "B_B") (pintype "passive"))
    )
    (net (code "253") (name "unconnected-(Q14-PadB)") (class "Default")
      (node (ref "Q14") (pin "B") (pinfunction "B_B") (pintype "passive"))
    )
    (net (code "254") (name "unconnected-(Q15-PadB)") (class "Default")
      (node (ref "Q15") (pin "B") (pinfunction "B_B") (pintype "passive"))
    )
    (net (code "255") (name "unconnected-(Q16-PadB)") (class "Default")
      (node (ref "Q16") (pin "B") (pinfunction "B_B") (pintype "passive"))
    )
  )
)
